# FMC_prototype.net
KiCad netlist of a schematic drawn in EAGLE
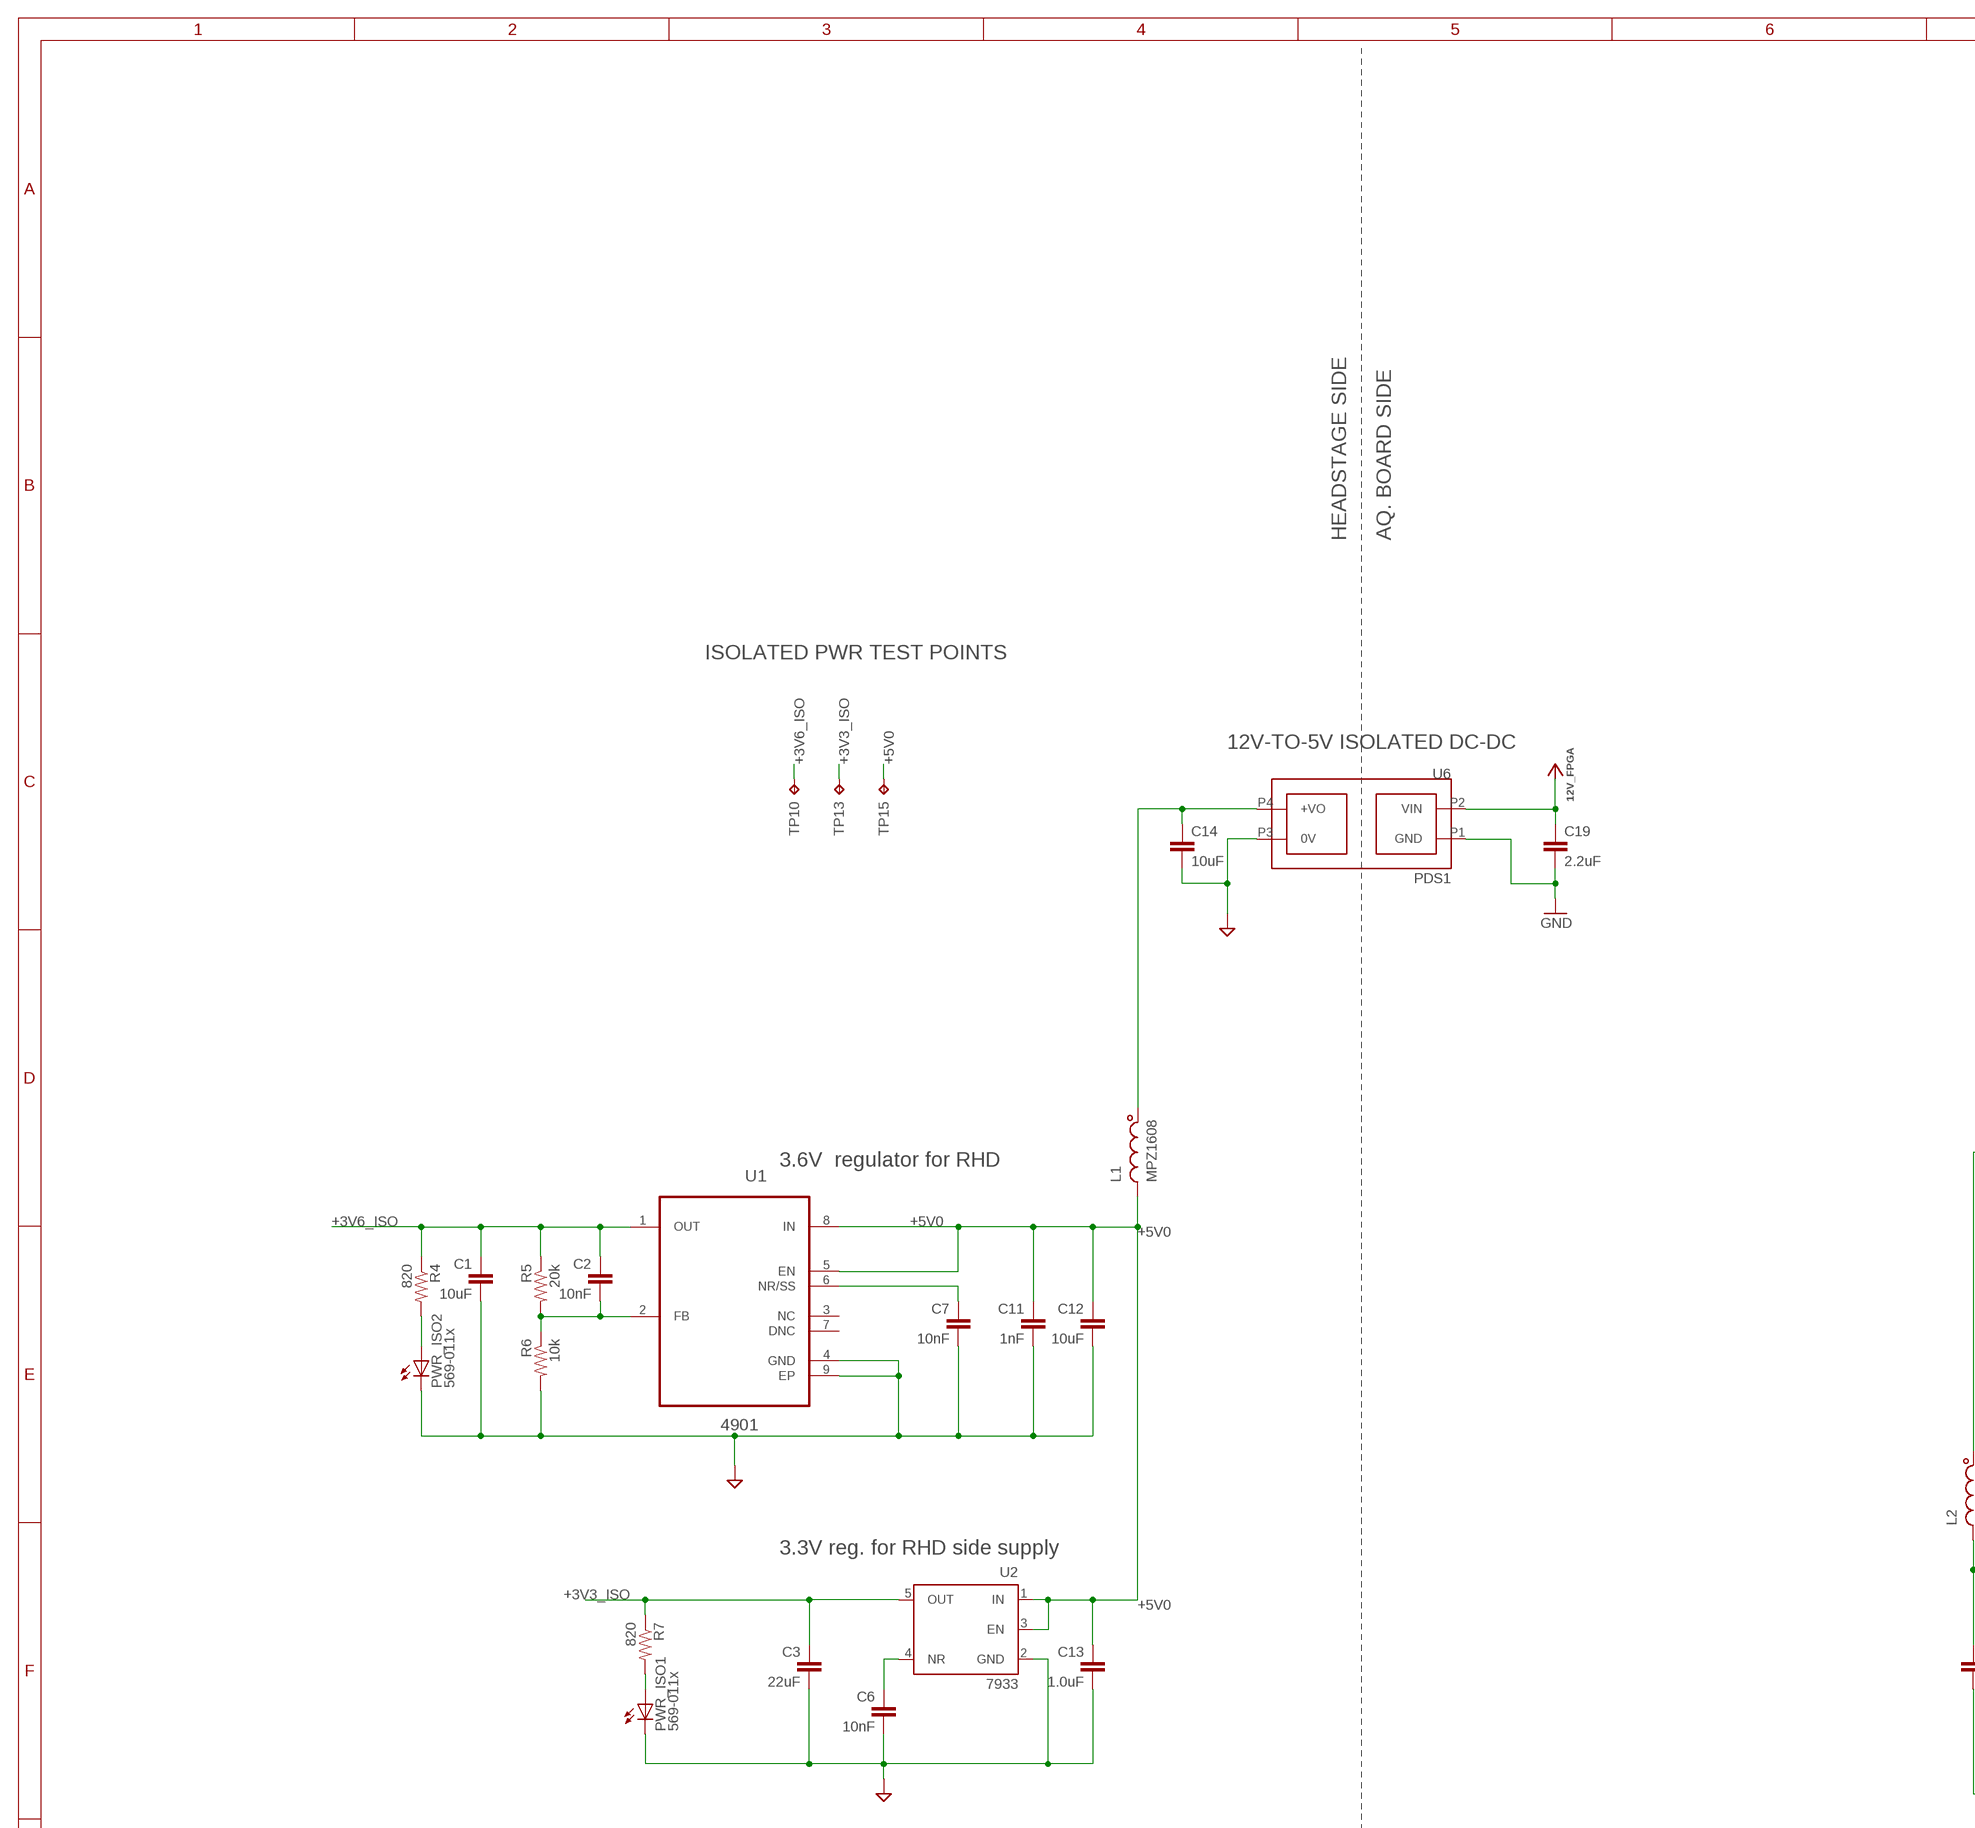
[diagram p0: schematic, sheet 1, part 1 of 3]
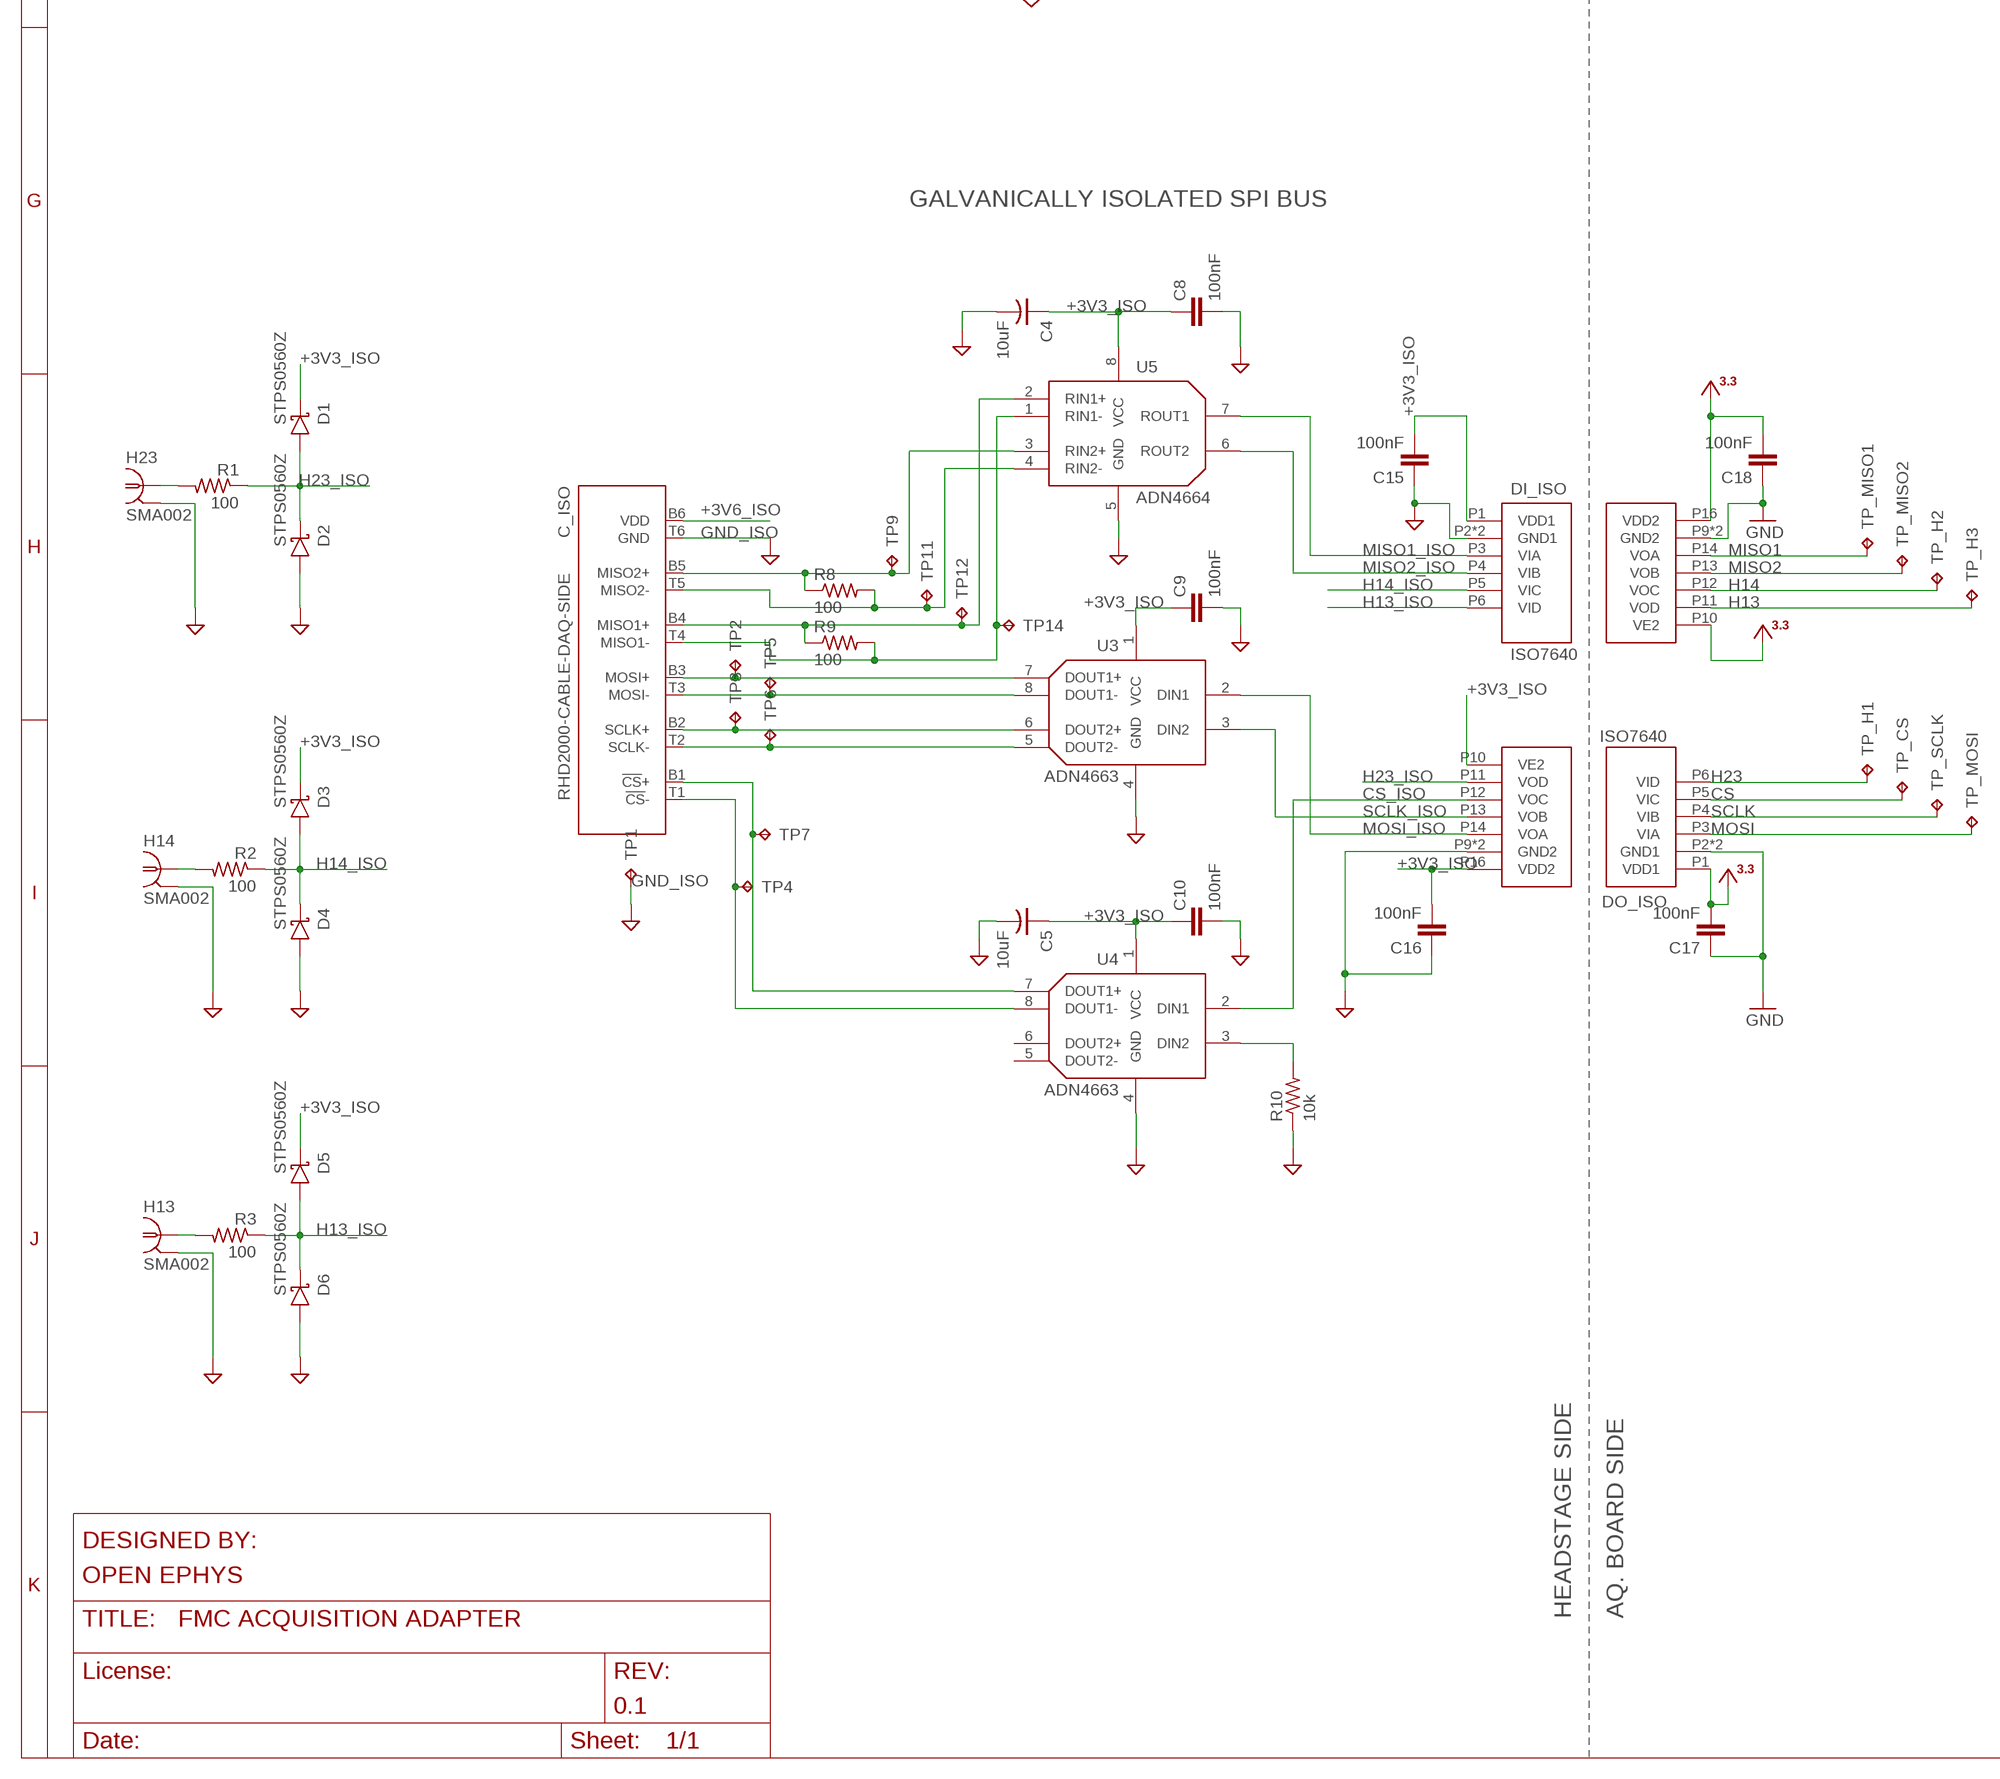
[diagram p1: schematic, sheet 1, part 2 of 3]
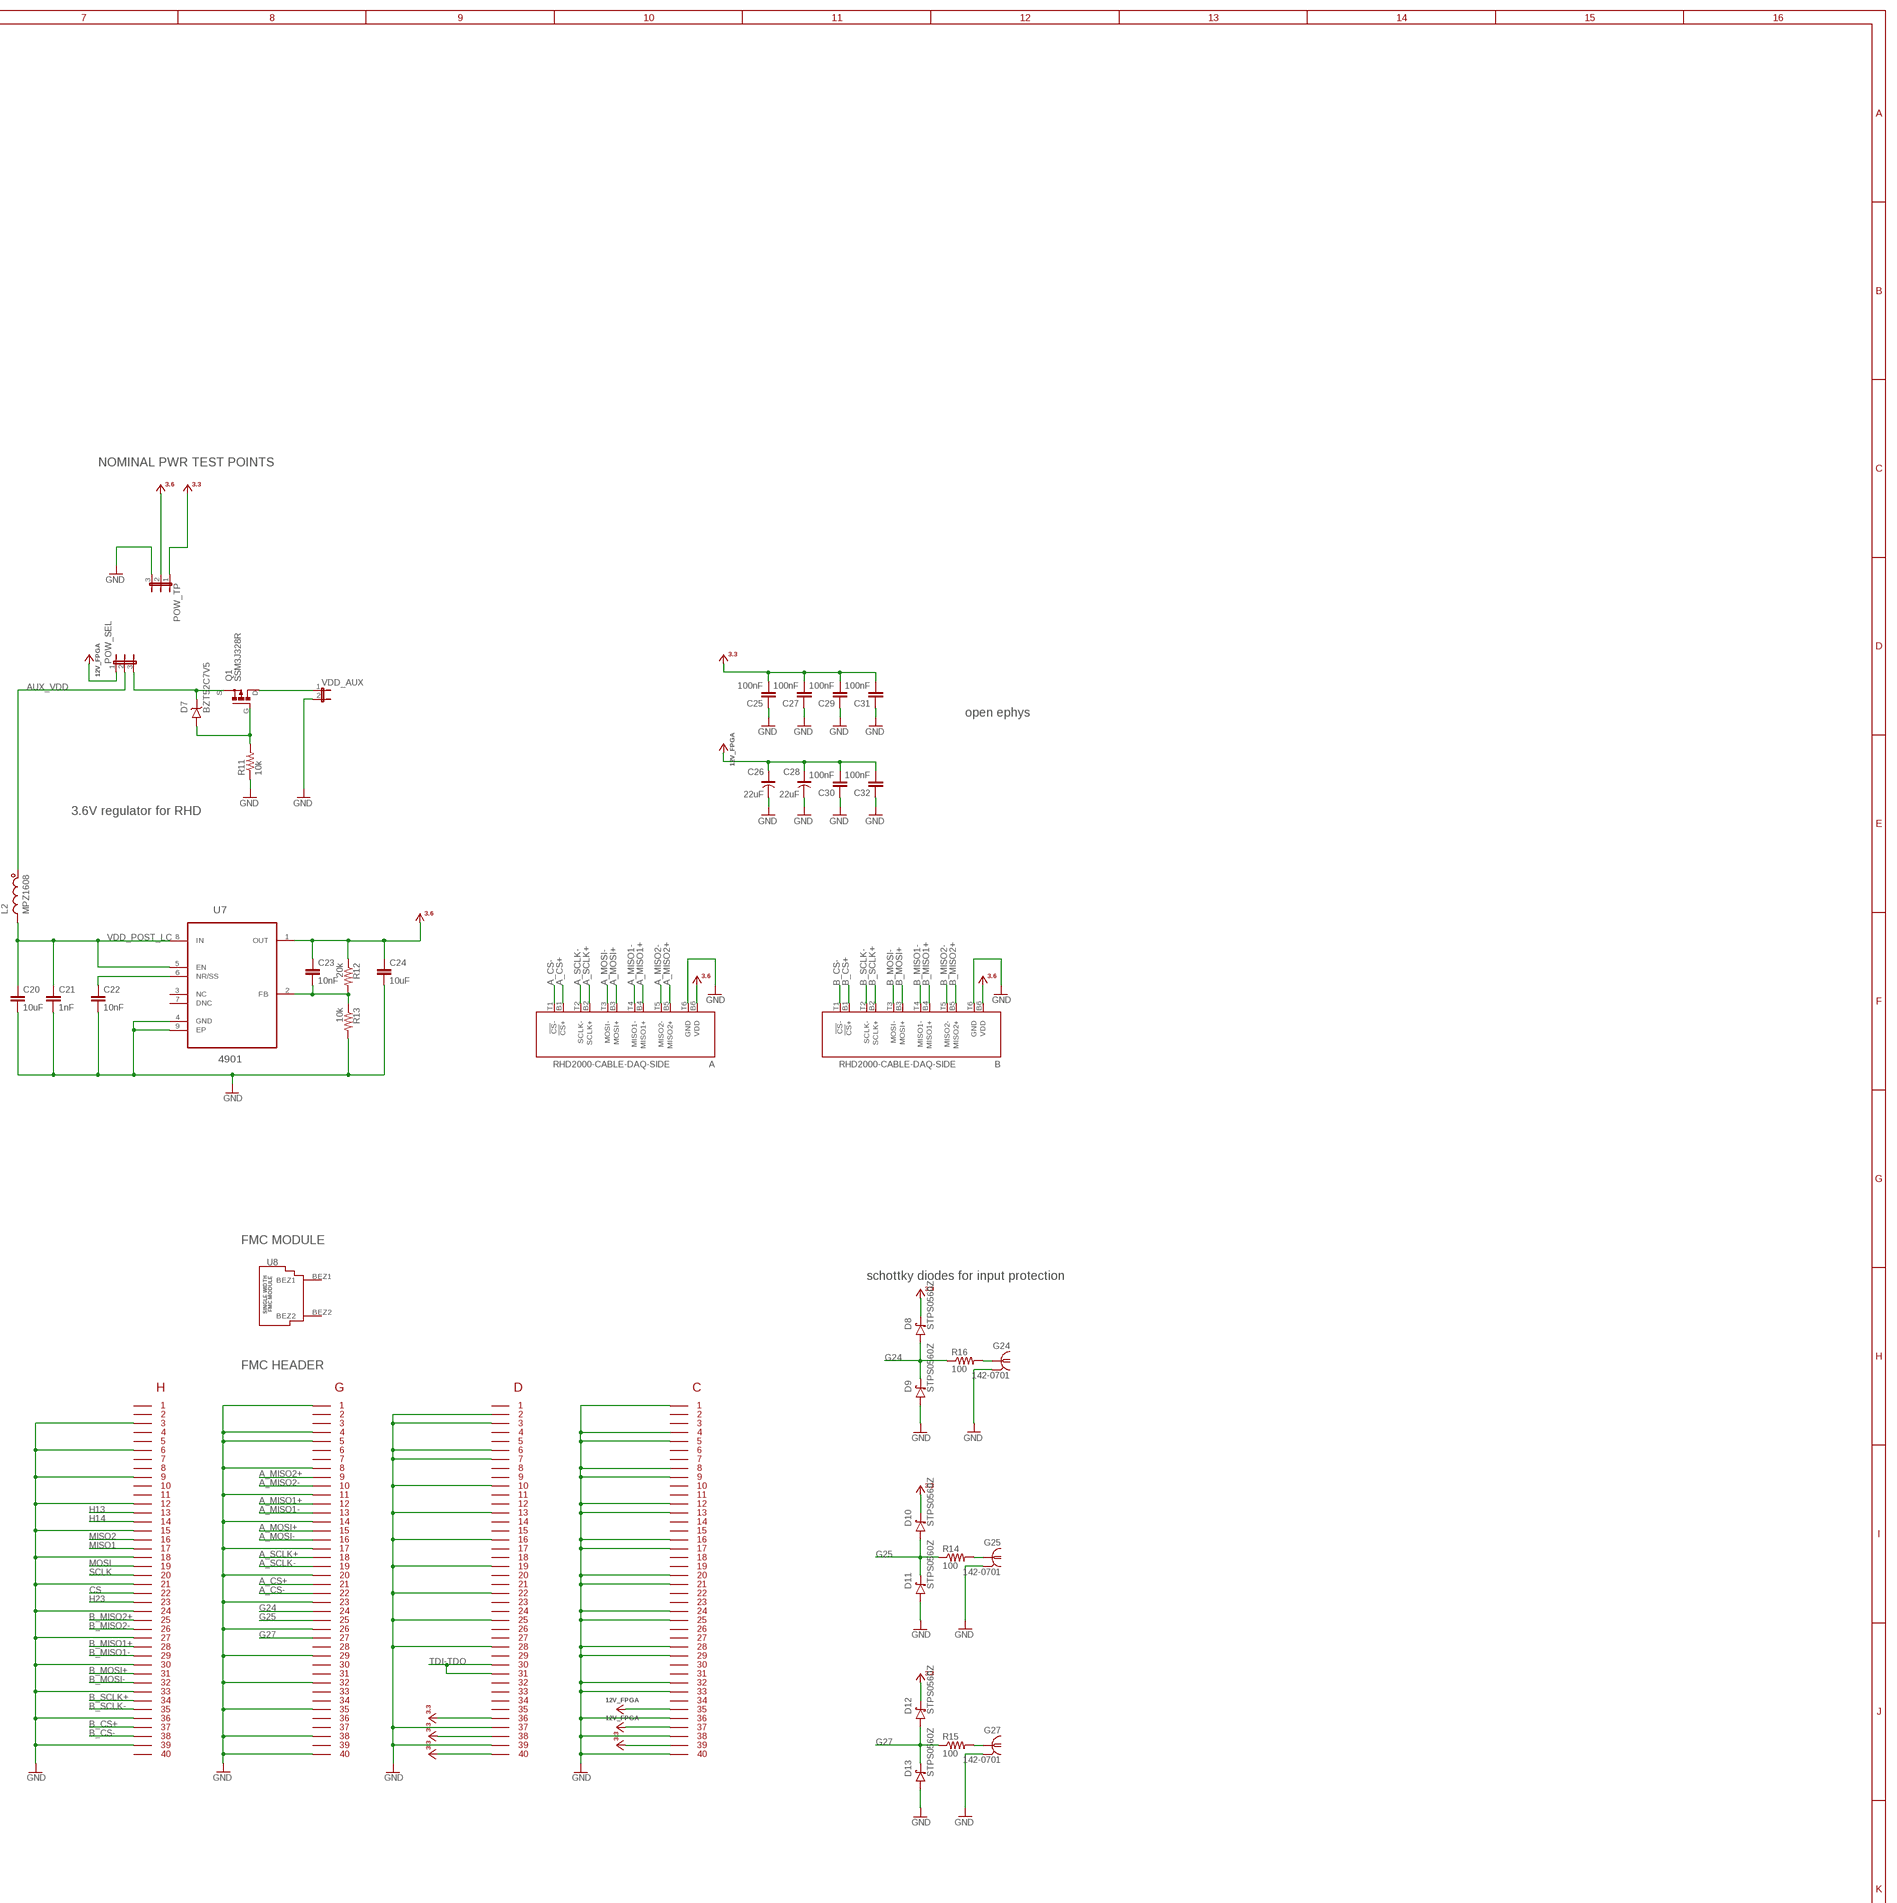
[diagram p2: schematic, sheet 1, part 3 of 3]

(export (version "E")
  (design (tool "Eeschema 10.0.6"))
  (components
    (comp (ref "A")
      (value "RHD2000-CABLE-DAQ-SIDE")
      (footprint "eagle-import:OMNETICS_PZN-12-AA")
      (libsource (lib "eagle-import") (part "RHD2000-CABLE-DAQ-SIDE"))
    )
    (comp (ref "B")
      (value "RHD2000-CABLE-DAQ-SIDE")
      (footprint "eagle-import:OMNETICS_PZN-12-AA")
      (libsource (lib "eagle-import") (part "RHD2000-CABLE-DAQ-SIDE"))
    )
    (comp (ref "C1")
      (value "10uF")
      (footprint "eagle-import:1206")
      (libsource (lib "eagle-import") (part "puggleboard_C_1206"))
    )
    (comp (ref "C2")
      (value "10nF")
      (footprint "eagle-import:0603")
      (libsource (lib "eagle-import") (part "jonnew_C_0603"))
    )
    (comp (ref "C3")
      (value "22uF")
      (footprint "eagle-import:1206")
      (libsource (lib "eagle-import") (part "C_1206"))
    )
    (comp (ref "C4")
      (value "10uF")
      (footprint "eagle-import:1206-POL")
      (libsource (lib "eagle-import") (part "C-POL_1206"))
    )
    (comp (ref "C5")
      (value "10uF")
      (footprint "eagle-import:1206-POL")
      (libsource (lib "eagle-import") (part "C-POL_1206"))
    )
    (comp (ref "C6")
      (value "10nF")
      (footprint "eagle-import:0603")
      (libsource (lib "eagle-import") (part "C_0603"))
    )
    (comp (ref "C7")
      (value "10nF")
      (footprint "eagle-import:0603")
      (libsource (lib "eagle-import") (part "jonnew_C_0603"))
    )
    (comp (ref "C8")
      (value "100nF")
      (footprint "eagle-import:0603")
      (libsource (lib "eagle-import") (part "C_0603"))
    )
    (comp (ref "C9")
      (value "100nF")
      (footprint "eagle-import:0603")
      (libsource (lib "eagle-import") (part "C_0603"))
    )
    (comp (ref "C10")
      (value "100nF")
      (footprint "eagle-import:0603")
      (libsource (lib "eagle-import") (part "C_0603"))
    )
    (comp (ref "C11")
      (value "1nF")
      (footprint "eagle-import:0603")
      (libsource (lib "eagle-import") (part "jonnew_C_0603"))
    )
    (comp (ref "C12")
      (value "10uF")
      (footprint "eagle-import:1206")
      (libsource (lib "eagle-import") (part "puggleboard_C_1206"))
    )
    (comp (ref "C13")
      (value "1.0uF")
      (footprint "eagle-import:0805")
      (libsource (lib "eagle-import") (part "C_0805"))
    )
    (comp (ref "C14")
      (value "10uF")
      (footprint "eagle-import:1206")
      (libsource (lib "eagle-import") (part "jonnew_C_1206"))
    )
    (comp (ref "C15")
      (value "100nF")
      (footprint "eagle-import:0603")
      (libsource (lib "eagle-import") (part "C_0603"))
    )
    (comp (ref "C16")
      (value "100nF")
      (footprint "eagle-import:0603")
      (libsource (lib "eagle-import") (part "C_0603"))
    )
    (comp (ref "C17")
      (value "100nF")
      (footprint "eagle-import:0603")
      (libsource (lib "eagle-import") (part "C_0603"))
    )
    (comp (ref "C18")
      (value "100nF")
      (footprint "eagle-import:0603")
      (libsource (lib "eagle-import") (part "C_0603"))
    )
    (comp (ref "C19")
      (value "2.2uF")
      (footprint "eagle-import:1206")
      (libsource (lib "eagle-import") (part "jonnew_C_1206"))
    )
    (comp (ref "C20")
      (value "10uF")
      (footprint "eagle-import:1206")
      (libsource (lib "eagle-import") (part "puggleboard_C_1206"))
    )
    (comp (ref "C21")
      (value "1nF")
      (footprint "eagle-import:0603")
      (libsource (lib "eagle-import") (part "jonnew_C_0603"))
    )
    (comp (ref "C22")
      (value "10nF")
      (footprint "eagle-import:0603")
      (libsource (lib "eagle-import") (part "jonnew_C_0603"))
    )
    (comp (ref "C23")
      (value "10nF")
      (footprint "eagle-import:0603")
      (libsource (lib "eagle-import") (part "jonnew_C_0603"))
    )
    (comp (ref "C24")
      (value "10uF")
      (footprint "eagle-import:1206")
      (libsource (lib "eagle-import") (part "puggleboard_C_1206"))
    )
    (comp (ref "C25")
      (value "100nF")
      (footprint "eagle-import:0603")
      (libsource (lib "eagle-import") (part "C_0603"))
    )
    (comp (ref "C26")
      (value "22uF")
      (footprint "eagle-import:1210-POL")
      (libsource (lib "eagle-import") (part "C-POL_1210"))
    )
    (comp (ref "C27")
      (value "100nF")
      (footprint "eagle-import:0603")
      (libsource (lib "eagle-import") (part "C_0603"))
    )
    (comp (ref "C28")
      (value "22uF")
      (footprint "eagle-import:1210-POL")
      (libsource (lib "eagle-import") (part "C-POL_1210"))
    )
    (comp (ref "C29")
      (value "100nF")
      (footprint "eagle-import:0603")
      (libsource (lib "eagle-import") (part "C_0603"))
    )
    (comp (ref "C30")
      (value "100nF")
      (footprint "eagle-import:0603")
      (libsource (lib "eagle-import") (part "C_0603"))
    )
    (comp (ref "C31")
      (value "100nF")
      (footprint "eagle-import:0603")
      (libsource (lib "eagle-import") (part "C_0603"))
    )
    (comp (ref "C32")
      (value "100nF")
      (footprint "eagle-import:0603")
      (libsource (lib "eagle-import") (part "C_0603"))
    )
    (comp (ref "C_ISO")
      (value "RHD2000-CABLE-DAQ-SIDE")
      (footprint "eagle-import:OMNETICS_PZN-12-AA")
      (libsource (lib "eagle-import") (part "RHD2000-CABLE-DAQ-SIDE"))
    )
    (comp (ref "D1")
      (value "STPS0560Z")
      (footprint "eagle-import:SOD123")
      (libsource (lib "eagle-import") (part "S-DIODESOD-123"))
    )
    (comp (ref "D2")
      (value "STPS0560Z")
      (footprint "eagle-import:SOD123")
      (libsource (lib "eagle-import") (part "S-DIODESOD-123"))
    )
    (comp (ref "D3")
      (value "STPS0560Z")
      (footprint "eagle-import:SOD123")
      (libsource (lib "eagle-import") (part "S-DIODESOD-123"))
    )
    (comp (ref "D4")
      (value "STPS0560Z")
      (footprint "eagle-import:SOD123")
      (libsource (lib "eagle-import") (part "S-DIODESOD-123"))
    )
    (comp (ref "D5")
      (value "STPS0560Z")
      (footprint "eagle-import:SOD123")
      (libsource (lib "eagle-import") (part "S-DIODESOD-123"))
    )
    (comp (ref "D6")
      (value "STPS0560Z")
      (footprint "eagle-import:SOD123")
      (libsource (lib "eagle-import") (part "S-DIODESOD-123"))
    )
    (comp (ref "D7")
      (value "BZT52C7V5")
      (footprint "eagle-import:SOD123")
      (libsource (lib "eagle-import") (part "Z-DIODE_SOD123"))
    )
    (comp (ref "D8")
      (value "STPS0560Z")
      (footprint "eagle-import:SOD123")
      (libsource (lib "eagle-import") (part "S-DIODESOD-123"))
    )
    (comp (ref "D9")
      (value "STPS0560Z")
      (footprint "eagle-import:SOD123")
      (libsource (lib "eagle-import") (part "S-DIODESOD-123"))
    )
    (comp (ref "D10")
      (value "STPS0560Z")
      (footprint "eagle-import:SOD123")
      (libsource (lib "eagle-import") (part "S-DIODESOD-123"))
    )
    (comp (ref "D11")
      (value "STPS0560Z")
      (footprint "eagle-import:SOD123")
      (libsource (lib "eagle-import") (part "S-DIODESOD-123"))
    )
    (comp (ref "D12")
      (value "STPS0560Z")
      (footprint "eagle-import:SOD123")
      (libsource (lib "eagle-import") (part "S-DIODESOD-123"))
    )
    (comp (ref "D13")
      (value "STPS0560Z")
      (footprint "eagle-import:SOD123")
      (libsource (lib "eagle-import") (part "S-DIODESOD-123"))
    )
    (comp (ref "DI_ISO")
      (value "ISO7640")
      (footprint "eagle-import:SOIC_WIDE_16")
      (libsource (lib "eagle-import") (part "ADUM3440"))
    )
    (comp (ref "DO_ISO")
      (value "ISO7640")
      (footprint "eagle-import:SOIC_WIDE_16")
      (libsource (lib "eagle-import") (part "ADUM3440"))
    )
    (comp (ref "FMC")
      (value "FMC_LPC_160_PIN")
      (footprint "eagle-import:FMC_LPC_MALE_WITH_SP601_BSILK")
      (libsource (lib "eagle-import") (part "FMC_LPC_160_PIN"))
    )
    (comp (ref "G24")
      (value "142-0701")
      (footprint "eagle-import:SMA_JACK_142-0701-201")
      (libsource (lib "eagle-import") (part "COAX_SMA-VERT"))
    )
    (comp (ref "G25")
      (value "142-0701")
      (footprint "eagle-import:SMA_JACK_142-0701-201")
      (libsource (lib "eagle-import") (part "COAX_SMA-VERT"))
    )
    (comp (ref "G27")
      (value "142-0701")
      (footprint "eagle-import:SMA_JACK_142-0701-201")
      (libsource (lib "eagle-import") (part "COAX_SMA-VERT"))
    )
    (comp (ref "H13")
      (value "SMA002")
      (footprint "eagle-import:SMA_JACK_CONREVSMA002-G")
      (libsource (lib "eagle-import") (part "COAX_CONREVSMA002-G"))
    )
    (comp (ref "H14")
      (value "SMA002")
      (footprint "eagle-import:SMA_JACK_CONREVSMA002-G")
      (libsource (lib "eagle-import") (part "COAX_CONREVSMA002-G"))
    )
    (comp (ref "H23")
      (value "SMA002")
      (footprint "eagle-import:SMA_JACK_CONREVSMA002-G")
      (libsource (lib "eagle-import") (part "COAX_CONREVSMA002-G"))
    )
    (comp (ref "L1")
      (value "MPZ1608")
      (footprint "eagle-import:0603")
      (libsource (lib "eagle-import") (part "L_0603"))
    )
    (comp (ref "L2")
      (value "MPZ1608")
      (footprint "eagle-import:0603")
      (libsource (lib "eagle-import") (part "L_0603"))
    )
    (comp (ref "POW_SEL")
      (value "JP3E")
      (footprint "eagle-import:JP3")
      (libsource (lib "eagle-import") (part "JP3E"))
    )
    (comp (ref "POW_TP")
      (value "JP3E")
      (footprint "eagle-import:JP3")
      (libsource (lib "eagle-import") (part "JP3E"))
    )
    (comp (ref "PWR_ISO")
      (value "569-011x")
      (footprint "eagle-import:569-011X-X00_LED_ARRAY")
      (libsource (lib "eagle-import") (part "LED_2X_VERTICAL"))
    )
    (comp (ref "Q1")
      (value "SSM3J328R")
      (footprint "eagle-import:SOT23-GSD")
      (libsource (lib "eagle-import") (part "P-MOSFET_SOT23-GSD"))
    )
    (comp (ref "R1")
      (value "100")
      (footprint "eagle-import:0603")
      (fields (field (name "MPN") "ERJ-3EKFxxxxV"))
      (libsource (lib "eagle-import") (part "jonnew_R_0603"))
    )
    (comp (ref "R2")
      (value "100")
      (footprint "eagle-import:0603")
      (fields (field (name "MPN") "ERJ-3EKFxxxxV"))
      (libsource (lib "eagle-import") (part "jonnew_R_0603"))
    )
    (comp (ref "R3")
      (value "100")
      (footprint "eagle-import:0603")
      (fields (field (name "MPN") "ERJ-3EKFxxxxV"))
      (libsource (lib "eagle-import") (part "jonnew_R_0603"))
    )
    (comp (ref "R4")
      (value "820")
      (footprint "eagle-import:0603")
      (libsource (lib "eagle-import") (part "R_0603"))
    )
    (comp (ref "R5")
      (value "20k")
      (footprint "eagle-import:0603")
      (fields (field (name "MPN") "ERJ-3EKFxxxxV"))
      (libsource (lib "eagle-import") (part "jonnew_R_0603"))
    )
    (comp (ref "R6")
      (value "10k")
      (footprint "eagle-import:0603")
      (fields (field (name "MPN") "ERJ-3EKFxxxxV"))
      (libsource (lib "eagle-import") (part "jonnew_R_0603"))
    )
    (comp (ref "R7")
      (value "820")
      (footprint "eagle-import:0603")
      (libsource (lib "eagle-import") (part "R_0603"))
    )
    (comp (ref "R8")
      (value "100")
      (footprint "eagle-import:0603")
      (libsource (lib "eagle-import") (part "R_0603"))
    )
    (comp (ref "R9")
      (value "100")
      (footprint "eagle-import:0603")
      (libsource (lib "eagle-import") (part "R_0603"))
    )
    (comp (ref "R10")
      (value "10k")
      (footprint "eagle-import:0603")
      (fields (field (name "MPN") "ERJ-3EKFxxxxV"))
      (libsource (lib "eagle-import") (part "jonnew_R_0603"))
    )
    (comp (ref "R11")
      (value "10k")
      (footprint "eagle-import:0603")
      (fields (field (name "MPN") "ERJ-3EKFxxxxV"))
      (libsource (lib "eagle-import") (part "jonnew_R_0603"))
    )
    (comp (ref "R12")
      (value "20k")
      (footprint "eagle-import:0603")
      (fields (field (name "MPN") "ERJ-3EKFxxxxV"))
      (libsource (lib "eagle-import") (part "jonnew_R_0603"))
    )
    (comp (ref "R13")
      (value "10k")
      (footprint "eagle-import:0603")
      (fields (field (name "MPN") "ERJ-3EKFxxxxV"))
      (libsource (lib "eagle-import") (part "jonnew_R_0603"))
    )
    (comp (ref "R14")
      (value "100")
      (footprint "eagle-import:0603")
      (fields (field (name "MPN") "ERJ-3EKFxxxxV"))
      (libsource (lib "eagle-import") (part "jonnew_R_0603"))
    )
    (comp (ref "R15")
      (value "100")
      (footprint "eagle-import:0603")
      (fields (field (name "MPN") "ERJ-3EKFxxxxV"))
      (libsource (lib "eagle-import") (part "jonnew_R_0603"))
    )
    (comp (ref "R16")
      (value "100")
      (footprint "eagle-import:0603")
      (fields (field (name "MPN") "ERJ-3EKFxxxxV"))
      (libsource (lib "eagle-import") (part "jonnew_R_0603"))
    )
    (comp (ref "TP1")
      (value "GND-ISO")
      (footprint "eagle-import:P1-13")
      (libsource (lib "eagle-import") (part "TPPAD1-13"))
    )
    (comp (ref "TP2")
      (value "MOSI+")
      (footprint "eagle-import:TP06R")
      (libsource (lib "eagle-import") (part "TPTP06R"))
    )
    (comp (ref "TP3")
      (value "SCLK+")
      (footprint "eagle-import:TP06R")
      (libsource (lib "eagle-import") (part "TPTP06R"))
    )
    (comp (ref "TP4")
      (value "CS-")
      (footprint "eagle-import:TP06R")
      (libsource (lib "eagle-import") (part "TPTP06R"))
    )
    (comp (ref "TP5")
      (value "MOSI-")
      (footprint "eagle-import:TP06R")
      (libsource (lib "eagle-import") (part "TPTP06R"))
    )
    (comp (ref "TP6")
      (value "SCLK-")
      (footprint "eagle-import:TP06R")
      (libsource (lib "eagle-import") (part "TPTP06R"))
    )
    (comp (ref "TP7")
      (value "CS+")
      (footprint "eagle-import:TP06R")
      (libsource (lib "eagle-import") (part "TPTP06R"))
    )
    (comp (ref "TP9")
      (value "MISO2+")
      (footprint "eagle-import:TP06R")
      (libsource (lib "eagle-import") (part "TPTP06R"))
    )
    (comp (ref "TP10")
      (value "+3V6")
      (footprint "eagle-import:TP06R")
      (libsource (lib "eagle-import") (part "TPTP06R"))
    )
    (comp (ref "TP11")
      (value "MISO2-")
      (footprint "eagle-import:TP06R")
      (libsource (lib "eagle-import") (part "TPTP06R"))
    )
    (comp (ref "TP12")
      (value "MISO1+")
      (footprint "eagle-import:TP06R")
      (libsource (lib "eagle-import") (part "TPTP06R"))
    )
    (comp (ref "TP13")
      (value "+3V3")
      (footprint "eagle-import:TP06R")
      (libsource (lib "eagle-import") (part "TPTP06R"))
    )
    (comp (ref "TP14")
      (value "MISO1-")
      (footprint "eagle-import:TP06R")
      (libsource (lib "eagle-import") (part "TPTP06R"))
    )
    (comp (ref "TP15")
      (value "+5V0")
      (footprint "eagle-import:TP06R")
      (libsource (lib "eagle-import") (part "TPTP06R"))
    )
    (comp (ref "TP_CS")
      (value "CS")
      (footprint "eagle-import:TP06R")
      (libsource (lib "eagle-import") (part "TPTP06R"))
    )
    (comp (ref "TP_H1")
      (value "H23")
      (footprint "eagle-import:TP06R")
      (libsource (lib "eagle-import") (part "TPTP06R"))
    )
    (comp (ref "TP_H2")
      (value "H14")
      (footprint "eagle-import:TP06R")
      (libsource (lib "eagle-import") (part "TPTP06R"))
    )
    (comp (ref "TP_H3")
      (value "H13")
      (footprint "eagle-import:TP06R")
      (libsource (lib "eagle-import") (part "TPTP06R"))
    )
    (comp (ref "TP_MISO1")
      (value "MISO1")
      (footprint "eagle-import:TP06R")
      (libsource (lib "eagle-import") (part "TPTP06R"))
    )
    (comp (ref "TP_MISO2")
      (value "MISO2")
      (footprint "eagle-import:TP06R")
      (libsource (lib "eagle-import") (part "TPTP06R"))
    )
    (comp (ref "TP_MOSI")
      (value "MOSI")
      (footprint "eagle-import:TP06R")
      (libsource (lib "eagle-import") (part "TPTP06R"))
    )
    (comp (ref "TP_SCLK")
      (value "SCLK")
      (footprint "eagle-import:TP06R")
      (libsource (lib "eagle-import") (part "TPTP06R"))
    )
    (comp (ref "U$1")
      (value "OPEN_EPHYS_LOGO")
      (footprint "eagle-import:OPEN_EPHYS_LOGO")
      (libsource (lib "eagle-import") (part "OPEN_EPHYS_LOGO"))
    )
    (comp (ref "U1")
      (value "4901")
      (footprint "eagle-import:SOP65P490X110-9N")
      (fields (field (name "MPN") "TPS7A4901DGNR"))
      (libsource (lib "eagle-import") (part "TPS7A4901DGNR"))
    )
    (comp (ref "U2")
      (value "7933")
      (footprint "eagle-import:SOT-23-5")
      (libsource (lib "eagle-import") (part "TPS79333"))
    )
    (comp (ref "U3")
      (value "ADN4663")
      (footprint "eagle-import:SOIC127P500X400-8N")
      (libsource (lib "eagle-import") (part "ADN4663_SOIC"))
    )
    (comp (ref "U4")
      (value "ADN4663")
      (footprint "eagle-import:SOIC127P500X400-8N")
      (libsource (lib "eagle-import") (part "ADN4663_SOIC"))
    )
    (comp (ref "U5")
      (value "ADN4664")
      (footprint "eagle-import:SOIC127P500X400-8N")
      (libsource (lib "eagle-import") (part "ADN4664_SOIC"))
    )
    (comp (ref "U6")
      (value "PDS1")
      (footprint "eagle-import:PDS1")
      (libsource (lib "eagle-import") (part "PDS1"))
    )
    (comp (ref "U7")
      (value "4901")
      (footprint "eagle-import:SOP65P490X110-9N")
      (fields (field (name "MPN") "TPS7A4901DGNR"))
      (libsource (lib "eagle-import") (part "TPS7A4901DGNR"))
    )
    (comp (ref "U8")
      (value "FMC_SINGLE_WIDTH_MODULE")
      (footprint "eagle-import:FMC_SINGLE_WIDTH_MODULE")
      (libsource (lib "eagle-import") (part "FMC_SINGLE_WIDTH_MODULE"))
    )
    (comp (ref "VDD_AUX")
      (value "JP2E_THRU-HOLE")
      (footprint "eagle-import:JP2")
      (libsource (lib "eagle-import") (part "JP2E_THRU-HOLE"))
    )
  )
  (nets
    (net (code "1") (name "+3V3") (class "Default")
      (node (ref "C17") (pin "2") (pinfunction "2_2") (pintype "passive"))
      (node (ref "C18") (pin "2") (pinfunction "2_2") (pintype "passive"))
      (node (ref "C25") (pin "2") (pinfunction "2_2") (pintype "passive"))
      (node (ref "C27") (pin "2") (pinfunction "2_2") (pintype "passive"))
      (node (ref "C29") (pin "2") (pinfunction "2_2") (pintype "passive"))
      (node (ref "C31") (pin "2") (pinfunction "2_2") (pintype "passive"))
      (node (ref "D10") (pin "C") (pinfunction "C_C") (pintype "passive"))
      (node (ref "D12") (pin "C") (pinfunction "C_C") (pintype "passive"))
      (node (ref "D8") (pin "C") (pinfunction "C_C") (pintype "passive"))
      (node (ref "DI_ISO") (pin "P10") (pinfunction "VE2_P10") (pintype "bidirectional"))
      (node (ref "DI_ISO") (pin "P16") (pinfunction "VDD2_P16") (pintype "bidirectional"))
      (node (ref "DO_ISO") (pin "P1") (pinfunction "VDD1_P1") (pintype "bidirectional"))
      (node (ref "FMC") (pin "P$116") (pinfunction "P$116_P$116") (pintype "bidirectional"))
      (node (ref "FMC") (pin "P$118") (pinfunction "P$118_P$118") (pintype "bidirectional"))
      (node (ref "FMC") (pin "P$120") (pinfunction "P$120_P$120") (pintype "bidirectional"))
      (node (ref "FMC") (pin "P$159") (pinfunction "P$159_P$159") (pintype "bidirectional"))
      (node (ref "POW_TP") (pin "1") (pinfunction "1_1") (pintype "passive"))
    )
    (net (code "2") (name "+3V6") (class "Default")
      (node (ref "A") (pin "B6") (pinfunction "VDD_B6") (pintype "bidirectional"))
      (node (ref "B") (pin "B6") (pinfunction "VDD_B6") (pintype "bidirectional"))
      (node (ref "C23") (pin "1") (pinfunction "1_1") (pintype "passive"))
      (node (ref "C24") (pin "1") (pinfunction "1_1") (pintype "passive"))
      (node (ref "POW_TP") (pin "2") (pinfunction "2_2") (pintype "passive"))
      (node (ref "R12") (pin "1") (pinfunction "1_1") (pintype "passive"))
      (node (ref "U7") (pin "1") (pinfunction "OUT_1") (pintype "passive"))
    )
    (net (code "3") (name "/+3V3_ISO") (class "Default")
      (node (ref "C10") (pin "1") (pinfunction "1_1") (pintype "passive"))
      (node (ref "C15") (pin "2") (pinfunction "2_2") (pintype "passive"))
      (node (ref "C16") (pin "2") (pinfunction "2_2") (pintype "passive"))
      (node (ref "C3") (pin "1") (pinfunction "1_1") (pintype "passive"))
      (node (ref "C4") (pin "+") (pinfunction "+_+") (pintype "passive"))
      (node (ref "C5") (pin "+") (pinfunction "+_+") (pintype "passive"))
      (node (ref "C8") (pin "1") (pinfunction "1_1") (pintype "passive"))
      (node (ref "C9") (pin "1") (pinfunction "1_1") (pintype "passive"))
      (node (ref "D1") (pin "C") (pinfunction "C_C") (pintype "passive"))
      (node (ref "D3") (pin "C") (pinfunction "C_C") (pintype "passive"))
      (node (ref "D5") (pin "C") (pinfunction "C_C") (pintype "passive"))
      (node (ref "DI_ISO") (pin "P1") (pinfunction "VDD1_P1") (pintype "bidirectional"))
      (node (ref "DO_ISO") (pin "P10") (pinfunction "VE2_P10") (pintype "bidirectional"))
      (node (ref "DO_ISO") (pin "P16") (pinfunction "VDD2_P16") (pintype "bidirectional"))
      (node (ref "R7") (pin "1") (pinfunction "1_1") (pintype "passive"))
      (node (ref "TP13") (pin "TP") (pinfunction "TP_TP") (pintype "input"))
      (node (ref "U2") (pin "5") (pinfunction "OUT_5") (pintype "passive"))
      (node (ref "U3") (pin "1") (pinfunction "VCC_1") (pintype "bidirectional"))
      (node (ref "U4") (pin "1") (pinfunction "VCC_1") (pintype "bidirectional"))
      (node (ref "U5") (pin "8") (pinfunction "VCC_8") (pintype "bidirectional"))
    )
    (net (code "4") (name "/+3V6_ISO") (class "Default")
      (node (ref "C1") (pin "1") (pinfunction "1_1") (pintype "passive"))
      (node (ref "C2") (pin "1") (pinfunction "1_1") (pintype "passive"))
      (node (ref "C_ISO") (pin "B6") (pinfunction "VDD_B6") (pintype "bidirectional"))
      (node (ref "R4") (pin "1") (pinfunction "1_1") (pintype "passive"))
      (node (ref "R5") (pin "1") (pinfunction "1_1") (pintype "passive"))
      (node (ref "TP10") (pin "TP") (pinfunction "TP_TP") (pintype "input"))
      (node (ref "U1") (pin "1") (pinfunction "OUT_1") (pintype "passive"))
    )
    (net (code "5") (name "/+5V0") (class "Default")
      (node (ref "C11") (pin "1") (pinfunction "1_1") (pintype "passive"))
      (node (ref "C12") (pin "1") (pinfunction "1_1") (pintype "passive"))
      (node (ref "C13") (pin "1") (pinfunction "1_1") (pintype "passive"))
      (node (ref "L1") (pin "2") (pinfunction "2_2") (pintype "passive"))
      (node (ref "TP15") (pin "TP") (pinfunction "TP_TP") (pintype "input"))
      (node (ref "U1") (pin "5") (pinfunction "EN_5") (pintype "input"))
      (node (ref "U1") (pin "8") (pinfunction "IN_8") (pintype "passive"))
      (node (ref "U2") (pin "1") (pinfunction "IN_1") (pintype "passive"))
      (node (ref "U2") (pin "3") (pinfunction "EN_3") (pintype "input"))
    )
    (net (code "6") (name "/12V_FPGA") (class "Default")
      (node (ref "C19") (pin "1") (pinfunction "1_1") (pintype "passive"))
      (node (ref "C26") (pin "+") (pinfunction "+_+") (pintype "passive"))
      (node (ref "C28") (pin "+") (pinfunction "+_+") (pintype "passive"))
      (node (ref "C30") (pin "2") (pinfunction "2_2") (pintype "passive"))
      (node (ref "C32") (pin "2") (pinfunction "2_2") (pintype "passive"))
      (node (ref "FMC") (pin "P$155") (pinfunction "P$155_P$155") (pintype "bidirectional"))
      (node (ref "FMC") (pin "P$157") (pinfunction "P$157_P$157") (pintype "bidirectional"))
      (node (ref "POW_SEL") (pin "1") (pinfunction "1_1") (pintype "passive"))
      (node (ref "U6") (pin "P2") (pinfunction "VIN_P2") (pintype "bidirectional"))
    )
    (net (code "7") (name "/AUX_VDD") (class "Default")
      (node (ref "L2") (pin "1") (pinfunction "1_1") (pintype "passive"))
      (node (ref "POW_SEL") (pin "2") (pinfunction "2_2") (pintype "passive"))
    )
    (net (code "8") (name "/A_CS+") (class "Default")
      (node (ref "A") (pin "B1") (pinfunction "~{CS}+_B1") (pintype "bidirectional"))
      (node (ref "FMC") (pin "P$61") (pinfunction "P$61_P$61") (pintype "bidirectional"))
    )
    (net (code "9") (name "/A_CS-") (class "Default")
      (node (ref "A") (pin "T1") (pinfunction "~{CS}-_T1") (pintype "bidirectional"))
      (node (ref "FMC") (pin "P$62") (pinfunction "P$62_P$62") (pintype "bidirectional"))
    )
    (net (code "10") (name "/A_MISO1+") (class "Default")
      (node (ref "A") (pin "B4") (pinfunction "MISO1+_B4") (pintype "bidirectional"))
      (node (ref "FMC") (pin "P$52") (pinfunction "P$52_P$52") (pintype "bidirectional"))
    )
    (net (code "11") (name "/A_MISO1-") (class "Default")
      (node (ref "A") (pin "T4") (pinfunction "MISO1-_T4") (pintype "bidirectional"))
      (node (ref "FMC") (pin "P$53") (pinfunction "P$53_P$53") (pintype "bidirectional"))
    )
    (net (code "12") (name "/A_MISO2+") (class "Default")
      (node (ref "A") (pin "B5") (pinfunction "MISO2+_B5") (pintype "bidirectional"))
      (node (ref "FMC") (pin "P$49") (pinfunction "P$49_P$49") (pintype "bidirectional"))
    )
    (net (code "13") (name "/A_MISO2-") (class "Default")
      (node (ref "A") (pin "T5") (pinfunction "MISO2-_T5") (pintype "bidirectional"))
      (node (ref "FMC") (pin "P$50") (pinfunction "P$50_P$50") (pintype "bidirectional"))
    )
    (net (code "14") (name "/A_MOSI+") (class "Default")
      (node (ref "A") (pin "B3") (pinfunction "MOSI+_B3") (pintype "bidirectional"))
      (node (ref "FMC") (pin "P$55") (pinfunction "P$55_P$55") (pintype "bidirectional"))
    )
    (net (code "15") (name "/A_MOSI-") (class "Default")
      (node (ref "A") (pin "T3") (pinfunction "MOSI-_T3") (pintype "bidirectional"))
      (node (ref "FMC") (pin "P$56") (pinfunction "P$56_P$56") (pintype "bidirectional"))
    )
    (net (code "16") (name "/A_SCLK+") (class "Default")
      (node (ref "A") (pin "B2") (pinfunction "SCLK+_B2") (pintype "bidirectional"))
      (node (ref "FMC") (pin "P$58") (pinfunction "P$58_P$58") (pintype "bidirectional"))
    )
    (net (code "17") (name "/A_SCLK-") (class "Default")
      (node (ref "A") (pin "T2") (pinfunction "SCLK-_T2") (pintype "bidirectional"))
      (node (ref "FMC") (pin "P$59") (pinfunction "P$59_P$59") (pintype "bidirectional"))
    )
    (net (code "18") (name "/B_CS+") (class "Default")
      (node (ref "B") (pin "B1") (pinfunction "~{CS}+_B1") (pintype "bidirectional"))
      (node (ref "FMC") (pin "P$37") (pinfunction "P$37_P$37") (pintype "bidirectional"))
    )
    (net (code "19") (name "/B_CS-") (class "Default")
      (node (ref "B") (pin "T1") (pinfunction "~{CS}-_T1") (pintype "bidirectional"))
      (node (ref "FMC") (pin "P$38") (pinfunction "P$38_P$38") (pintype "bidirectional"))
    )
    (net (code "20") (name "/B_MISO1+") (class "Default")
      (node (ref "B") (pin "B4") (pinfunction "MISO1+_B4") (pintype "bidirectional"))
      (node (ref "FMC") (pin "P$28") (pinfunction "P$28_P$28") (pintype "bidirectional"))
    )
    (net (code "21") (name "/B_MISO1-") (class "Default")
      (node (ref "B") (pin "T4") (pinfunction "MISO1-_T4") (pintype "bidirectional"))
      (node (ref "FMC") (pin "P$29") (pinfunction "P$29_P$29") (pintype "bidirectional"))
    )
    (net (code "22") (name "/B_MISO2+") (class "Default")
      (node (ref "B") (pin "B5") (pinfunction "MISO2+_B5") (pintype "bidirectional"))
      (node (ref "FMC") (pin "P$25") (pinfunction "P$25_P$25") (pintype "bidirectional"))
    )
    (net (code "23") (name "/B_MISO2-") (class "Default")
      (node (ref "B") (pin "T5") (pinfunction "MISO2-_T5") (pintype "bidirectional"))
      (node (ref "FMC") (pin "P$26") (pinfunction "P$26_P$26") (pintype "bidirectional"))
    )
    (net (code "24") (name "/B_MOSI+") (class "Default")
      (node (ref "B") (pin "B3") (pinfunction "MOSI+_B3") (pintype "bidirectional"))
      (node (ref "FMC") (pin "P$31") (pinfunction "P$31_P$31") (pintype "bidirectional"))
    )
    (net (code "25") (name "/B_MOSI-") (class "Default")
      (node (ref "B") (pin "T3") (pinfunction "MOSI-_T3") (pintype "bidirectional"))
      (node (ref "FMC") (pin "P$32") (pinfunction "P$32_P$32") (pintype "bidirectional"))
    )
    (net (code "26") (name "/B_SCLK+") (class "Default")
      (node (ref "B") (pin "B2") (pinfunction "SCLK+_B2") (pintype "bidirectional"))
      (node (ref "FMC") (pin "P$34") (pinfunction "P$34_P$34") (pintype "bidirectional"))
    )
    (net (code "27") (name "/B_SCLK-") (class "Default")
      (node (ref "B") (pin "T2") (pinfunction "SCLK-_T2") (pintype "bidirectional"))
      (node (ref "FMC") (pin "P$35") (pinfunction "P$35_P$35") (pintype "bidirectional"))
    )
    (net (code "28") (name "/CS") (class "Default")
      (node (ref "DO_ISO") (pin "P5") (pinfunction "VIC_P5") (pintype "bidirectional"))
      (node (ref "FMC") (pin "P$22") (pinfunction "P$22_P$22") (pintype "bidirectional"))
      (node (ref "TP_CS") (pin "TP") (pinfunction "TP_TP") (pintype "input"))
    )
    (net (code "29") (name "/CS_ISO") (class "Default")
      (node (ref "DO_ISO") (pin "P12") (pinfunction "VOC_P12") (pintype "bidirectional"))
      (node (ref "U4") (pin "2") (pinfunction "DIN1_2") (pintype "bidirectional"))
    )
    (net (code "30") (name "/G24") (class "Default")
      (node (ref "D8") (pin "A") (pinfunction "A_A") (pintype "passive"))
      (node (ref "D9") (pin "C") (pinfunction "C_C") (pintype "passive"))
      (node (ref "FMC") (pin "P$64") (pinfunction "P$64_P$64") (pintype "bidirectional"))
      (node (ref "R16") (pin "1") (pinfunction "1_1") (pintype "passive"))
    )
    (net (code "31") (name "/G25") (class "Default")
      (node (ref "D10") (pin "A") (pinfunction "A_A") (pintype "passive"))
      (node (ref "D11") (pin "C") (pinfunction "C_C") (pintype "passive"))
      (node (ref "FMC") (pin "P$65") (pinfunction "P$65_P$65") (pintype "bidirectional"))
      (node (ref "R14") (pin "1") (pinfunction "1_1") (pintype "passive"))
    )
    (net (code "32") (name "/G27") (class "Default")
      (node (ref "D12") (pin "A") (pinfunction "A_A") (pintype "passive"))
      (node (ref "D13") (pin "C") (pinfunction "C_C") (pintype "passive"))
      (node (ref "FMC") (pin "P$67") (pinfunction "P$67_P$67") (pintype "bidirectional"))
      (node (ref "R15") (pin "1") (pinfunction "1_1") (pintype "passive"))
    )
    (net (code "33") (name "/H13") (class "Default")
      (node (ref "DI_ISO") (pin "P11") (pinfunction "VOD_P11") (pintype "bidirectional"))
      (node (ref "FMC") (pin "P$13") (pinfunction "P$13_P$13") (pintype "bidirectional"))
      (node (ref "TP_H3") (pin "TP") (pinfunction "TP_TP") (pintype "input"))
    )
    (net (code "34") (name "/H13_ISO") (class "Default")
      (node (ref "D5") (pin "A") (pinfunction "A_A") (pintype "passive"))
      (node (ref "D6") (pin "C") (pinfunction "C_C") (pintype "passive"))
      (node (ref "DI_ISO") (pin "P6") (pinfunction "VID_P6") (pintype "bidirectional"))
      (node (ref "R3") (pin "1") (pinfunction "1_1") (pintype "passive"))
    )
    (net (code "35") (name "/H14") (class "Default")
      (node (ref "DI_ISO") (pin "P12") (pinfunction "VOC_P12") (pintype "bidirectional"))
      (node (ref "FMC") (pin "P$14") (pinfunction "P$14_P$14") (pintype "bidirectional"))
      (node (ref "TP_H2") (pin "TP") (pinfunction "TP_TP") (pintype "input"))
    )
    (net (code "36") (name "/H14_ISO") (class "Default")
      (node (ref "D3") (pin "A") (pinfunction "A_A") (pintype "passive"))
      (node (ref "D4") (pin "C") (pinfunction "C_C") (pintype "passive"))
      (node (ref "DI_ISO") (pin "P5") (pinfunction "VIC_P5") (pintype "bidirectional"))
      (node (ref "R2") (pin "1") (pinfunction "1_1") (pintype "passive"))
    )
    (net (code "37") (name "/H23") (class "Default")
      (node (ref "DO_ISO") (pin "P6") (pinfunction "VID_P6") (pintype "bidirectional"))
      (node (ref "FMC") (pin "P$23") (pinfunction "P$23_P$23") (pintype "bidirectional"))
      (node (ref "TP_H1") (pin "TP") (pinfunction "TP_TP") (pintype "input"))
    )
    (net (code "38") (name "/H23_ISO") (class "Default")
      (node (ref "D1") (pin "A") (pinfunction "A_A") (pintype "passive"))
      (node (ref "D2") (pin "C") (pinfunction "C_C") (pintype "passive"))
      (node (ref "DO_ISO") (pin "P11") (pinfunction "VOD_P11") (pintype "bidirectional"))
      (node (ref "R1") (pin "1") (pinfunction "1_1") (pintype "passive"))
    )
    (net (code "39") (name "/MISO1") (class "Default")
      (node (ref "DI_ISO") (pin "P14") (pinfunction "VOA_P14") (pintype "bidirectional"))
      (node (ref "FMC") (pin "P$17") (pinfunction "P$17_P$17") (pintype "bidirectional"))
      (node (ref "TP_MISO1") (pin "TP") (pinfunction "TP_TP") (pintype "input"))
    )
    (net (code "40") (name "/MISO1_ISO") (class "Default")
      (node (ref "DI_ISO") (pin "P3") (pinfunction "VIA_P3") (pintype "bidirectional"))
      (node (ref "U5") (pin "7") (pinfunction "ROUT1_7") (pintype "bidirectional"))
    )
    (net (code "41") (name "/MISO2") (class "Default")
      (node (ref "DI_ISO") (pin "P13") (pinfunction "VOB_P13") (pintype "bidirectional"))
      (node (ref "FMC") (pin "P$16") (pinfunction "P$16_P$16") (pintype "bidirectional"))
      (node (ref "TP_MISO2") (pin "TP") (pinfunction "TP_TP") (pintype "input"))
    )
    (net (code "42") (name "/MISO2_ISO") (class "Default")
      (node (ref "DI_ISO") (pin "P4") (pinfunction "VIB_P4") (pintype "bidirectional"))
      (node (ref "U5") (pin "6") (pinfunction "ROUT2_6") (pintype "bidirectional"))
    )
    (net (code "43") (name "/MOSI") (class "Default")
      (node (ref "DO_ISO") (pin "P3") (pinfunction "VIA_P3") (pintype "bidirectional"))
      (node (ref "FMC") (pin "P$19") (pinfunction "P$19_P$19") (pintype "bidirectional"))
      (node (ref "TP_MOSI") (pin "TP") (pinfunction "TP_TP") (pintype "input"))
    )
    (net (code "44") (name "/MOSI_ISO") (class "Default")
      (node (ref "DO_ISO") (pin "P14") (pinfunction "VOA_P14") (pintype "bidirectional"))
      (node (ref "U3") (pin "2") (pinfunction "DIN1_2") (pintype "bidirectional"))
    )
    (net (code "45") (name "/SCLK") (class "Default")
      (node (ref "DO_ISO") (pin "P4") (pinfunction "VIB_P4") (pintype "bidirectional"))
      (node (ref "FMC") (pin "P$20") (pinfunction "P$20_P$20") (pintype "bidirectional"))
      (node (ref "TP_SCLK") (pin "TP") (pinfunction "TP_TP") (pintype "input"))
    )
    (net (code "46") (name "/SCLK_ISO") (class "Default")
      (node (ref "DO_ISO") (pin "P13") (pinfunction "VOB_P13") (pintype "bidirectional"))
      (node (ref "U3") (pin "3") (pinfunction "DIN2_3") (pintype "bidirectional"))
    )
    (net (code "47") (name "/TDI-TDO") (class "Default")
      (node (ref "FMC") (pin "P$110") (pinfunction "P$110_P$110") (pintype "bidirectional"))
      (node (ref "FMC") (pin "P$111") (pinfunction "P$111_P$111") (pintype "bidirectional"))
    )
    (net (code "48") (name "/VDD_POST_LC") (class "Default")
      (node (ref "C20") (pin "1") (pinfunction "1_1") (pintype "passive"))
      (node (ref "C21") (pin "1") (pinfunction "1_1") (pintype "passive"))
      (node (ref "L2") (pin "2") (pinfunction "2_2") (pintype "passive"))
      (node (ref "U7") (pin "5") (pinfunction "EN_5") (pintype "input"))
      (node (ref "U7") (pin "8") (pinfunction "IN_8") (pintype "passive"))
    )
    (net (code "49") (name "GND") (class "Default")
      (node (ref "A") (pin "T6") (pinfunction "GND_T6") (pintype "power_in"))
      (node (ref "B") (pin "T6") (pinfunction "GND_T6") (pintype "power_in"))
      (node (ref "C17") (pin "1") (pinfunction "1_1") (pintype "passive"))
      (node (ref "C18") (pin "1") (pinfunction "1_1") (pintype "passive"))
      (node (ref "C19") (pin "2") (pinfunction "2_2") (pintype "passive"))
      (node (ref "C20") (pin "2") (pinfunction "2_2") (pintype "passive"))
      (node (ref "C21") (pin "2") (pinfunction "2_2") (pintype "passive"))
      (node (ref "C22") (pin "2") (pinfunction "2_2") (pintype "passive"))
      (node (ref "C24") (pin "2") (pinfunction "2_2") (pintype "passive"))
      (node (ref "C25") (pin "1") (pinfunction "1_1") (pintype "passive"))
      (node (ref "C26") (pin "-") (pinfunction "-_-") (pintype "passive"))
      (node (ref "C27") (pin "1") (pinfunction "1_1") (pintype "passive"))
      (node (ref "C28") (pin "-") (pinfunction "-_-") (pintype "passive"))
      (node (ref "C29") (pin "1") (pinfunction "1_1") (pintype "passive"))
      (node (ref "C30") (pin "1") (pinfunction "1_1") (pintype "passive"))
      (node (ref "C31") (pin "1") (pinfunction "1_1") (pintype "passive"))
      (node (ref "C32") (pin "1") (pinfunction "1_1") (pintype "passive"))
      (node (ref "D11") (pin "A") (pinfunction "A_A") (pintype "passive"))
      (node (ref "D13") (pin "A") (pinfunction "A_A") (pintype "passive"))
      (node (ref "D9") (pin "A") (pinfunction "A_A") (pintype "passive"))
      (node (ref "DI_ISO") (pin "P15") (pinfunction "GND2_P15") (pintype "bidirectional"))
      (node (ref "DI_ISO") (pin "P9") (pinfunction "GND2_P9") (pintype "bidirectional"))
      (node (ref "DO_ISO") (pin "P2") (pinfunction "GND1_P2") (pintype "bidirectional"))
      (node (ref "DO_ISO") (pin "P8") (pinfunction "GND1_P8") (pintype "bidirectional"))
      (node (ref "FMC") (pin "P$102") (pinfunction "P$102_P$102") (pintype "bidirectional"))
      (node (ref "FMC") (pin "P$105") (pinfunction "P$105_P$105") (pintype "bidirectional"))
      (node (ref "FMC") (pin "P$108") (pinfunction "P$108_P$108") (pintype "bidirectional"))
      (node (ref "FMC") (pin "P$117") (pinfunction "P$117_P$117") (pintype "bidirectional"))
      (node (ref "FMC") (pin "P$119") (pinfunction "P$119_P$119") (pintype "bidirectional"))
      (node (ref "FMC") (pin "P$12") (pinfunction "P$12_P$12") (pintype "bidirectional"))
      (node (ref "FMC") (pin "P$121") (pinfunction "P$121_P$121") (pintype "bidirectional"))
      (node (ref "FMC") (pin "P$124") (pinfunction "P$124_P$124") (pintype "bidirectional"))
      (node (ref "FMC") (pin "P$125") (pinfunction "P$125_P$125") (pintype "bidirectional"))
      (node (ref "FMC") (pin "P$128") (pinfunction "P$128_P$128") (pintype "bidirectional"))
      (node (ref "FMC") (pin "P$129") (pinfunction "P$129_P$129") (pintype "bidirectional"))
      (node (ref "FMC") (pin "P$132") (pinfunction "P$132_P$132") (pintype "bidirectional"))
      (node (ref "FMC") (pin "P$133") (pinfunction "P$133_P$133") (pintype "bidirectional"))
      (node (ref "FMC") (pin "P$136") (pinfunction "P$136_P$136") (pintype "bidirectional"))
      (node (ref "FMC") (pin "P$137") (pinfunction "P$137_P$137") (pintype "bidirectional"))
      (node (ref "FMC") (pin "P$140") (pinfunction "P$140_P$140") (pintype "bidirectional"))
      (node (ref "FMC") (pin "P$141") (pinfunction "P$141_P$141") (pintype "bidirectional"))
      (node (ref "FMC") (pin "P$144") (pinfunction "P$144_P$144") (pintype "bidirectional"))
      (node (ref "FMC") (pin "P$145") (pinfunction "P$145_P$145") (pintype "bidirectional"))
      (node (ref "FMC") (pin "P$148") (pinfunction "P$148_P$148") (pintype "bidirectional"))
      (node (ref "FMC") (pin "P$149") (pinfunction "P$149_P$149") (pintype "bidirectional"))
      (node (ref "FMC") (pin "P$15") (pinfunction "P$15_P$15") (pintype "bidirectional"))
      (node (ref "FMC") (pin "P$152") (pinfunction "P$152_P$152") (pintype "bidirectional"))
      (node (ref "FMC") (pin "P$153") (pinfunction "P$153_P$153") (pintype "bidirectional"))
      (node (ref "FMC") (pin "P$156") (pinfunction "P$156_P$156") (pintype "bidirectional"))
      (node (ref "FMC") (pin "P$158") (pinfunction "P$158_P$158") (pintype "bidirectional"))
      (node (ref "FMC") (pin "P$160") (pinfunction "P$160_P$160") (pintype "bidirectional"))
      (node (ref "FMC") (pin "P$18") (pinfunction "P$18_P$18") (pintype "bidirectional"))
      (node (ref "FMC") (pin "P$21") (pinfunction "P$21_P$21") (pintype "bidirectional"))
      (node (ref "FMC") (pin "P$24") (pinfunction "P$24_P$24") (pintype "bidirectional"))
      (node (ref "FMC") (pin "P$27") (pinfunction "P$27_P$27") (pintype "bidirectional"))
      (node (ref "FMC") (pin "P$3") (pinfunction "P$3_P$3") (pintype "bidirectional"))
      (node (ref "FMC") (pin "P$30") (pinfunction "P$30_P$30") (pintype "bidirectional"))
      (node (ref "FMC") (pin "P$33") (pinfunction "P$33_P$33") (pintype "bidirectional"))
      (node (ref "FMC") (pin "P$36") (pinfunction "P$36_P$36") (pintype "bidirectional"))
      (node (ref "FMC") (pin "P$39") (pinfunction "P$39_P$39") (pintype "bidirectional"))
      (node (ref "FMC") (pin "P$41") (pinfunction "P$41_P$41") (pintype "bidirectional"))
      (node (ref "FMC") (pin "P$44") (pinfunction "P$44_P$44") (pintype "bidirectional"))
      (node (ref "FMC") (pin "P$45") (pinfunction "P$45_P$45") (pintype "bidirectional"))
      (node (ref "FMC") (pin "P$48") (pinfunction "P$48_P$48") (pintype "bidirectional"))
      (node (ref "FMC") (pin "P$51") (pinfunction "P$51_P$51") (pintype "bidirectional"))
      (node (ref "FMC") (pin "P$54") (pinfunction "P$54_P$54") (pintype "bidirectional"))
      (node (ref "FMC") (pin "P$57") (pinfunction "P$57_P$57") (pintype "bidirectional"))
      (node (ref "FMC") (pin "P$6") (pinfunction "P$6_P$6") (pintype "bidirectional"))
      (node (ref "FMC") (pin "P$60") (pinfunction "P$60_P$60") (pintype "bidirectional"))
      (node (ref "FMC") (pin "P$63") (pinfunction "P$63_P$63") (pintype "bidirectional"))
      (node (ref "FMC") (pin "P$66") (pinfunction "P$66_P$66") (pintype "bidirectional"))
      (node (ref "FMC") (pin "P$69") (pinfunction "P$69_P$69") (pintype "bidirectional"))
      (node (ref "FMC") (pin "P$72") (pinfunction "P$72_P$72") (pintype "bidirectional"))
      (node (ref "FMC") (pin "P$75") (pinfunction "P$75_P$75") (pintype "bidirectional"))
      (node (ref "FMC") (pin "P$78") (pinfunction "P$78_P$78") (pintype "bidirectional"))
      (node (ref "FMC") (pin "P$80") (pinfunction "P$80_P$80") (pintype "bidirectional"))
      (node (ref "FMC") (pin "P$82") (pinfunction "P$82_P$82") (pintype "bidirectional"))
      (node (ref "FMC") (pin "P$83") (pinfunction "P$83_P$83") (pintype "bidirectional"))
      (node (ref "FMC") (pin "P$86") (pinfunction "P$86_P$86") (pintype "bidirectional"))
      (node (ref "FMC") (pin "P$87") (pinfunction "P$87_P$87") (pintype "bidirectional"))
      (node (ref "FMC") (pin "P$9") (pinfunction "P$9_P$9") (pintype "bidirectional"))
      (node (ref "FMC") (pin "P$90") (pinfunction "P$90_P$90") (pintype "bidirectional"))
      (node (ref "FMC") (pin "P$93") (pinfunction "P$93_P$93") (pintype "bidirectional"))
      (node (ref "FMC") (pin "P$96") (pinfunction "P$96_P$96") (pintype "bidirectional"))
      (node (ref "FMC") (pin "P$99") (pinfunction "P$99_P$99") (pintype "bidirectional"))
      (node (ref "G24") (pin "GND$1") (pinfunction "2_GND$1") (pintype "passive"))
      (node (ref "G24") (pin "GND$2") (pinfunction "2_GND$2") (pintype "passive"))
      (node (ref "G24") (pin "GND$3") (pinfunction "2_GND$3") (pintype "passive"))
      (node (ref "G24") (pin "GND$4") (pinfunction "2_GND$4") (pintype "passive"))
      (node (ref "G25") (pin "GND$1") (pinfunction "2_GND$1") (pintype "passive"))
      (node (ref "G25") (pin "GND$2") (pinfunction "2_GND$2") (pintype "passive"))
      (node (ref "G25") (pin "GND$3") (pinfunction "2_GND$3") (pintype "passive"))
      (node (ref "G25") (pin "GND$4") (pinfunction "2_GND$4") (pintype "passive"))
      (node (ref "G27") (pin "GND$1") (pinfunction "2_GND$1") (pintype "passive"))
      (node (ref "G27") (pin "GND$2") (pinfunction "2_GND$2") (pintype "passive"))
      (node (ref "G27") (pin "GND$3") (pinfunction "2_GND$3") (pintype "passive"))
      (node (ref "G27") (pin "GND$4") (pinfunction "2_GND$4") (pintype "passive"))
      (node (ref "POW_TP") (pin "3") (pinfunction "3_3") (pintype "passive"))
      (node (ref "R11") (pin "1") (pinfunction "1_1") (pintype "passive"))
      (node (ref "R13") (pin "2") (pinfunction "2_2") (pintype "passive"))
      (node (ref "U6") (pin "P1") (pinfunction "GND_P1") (pintype "bidirectional"))
      (node (ref "U7") (pin "4") (pinfunction "GND_4") (pintype "passive"))
      (node (ref "U7") (pin "9") (pinfunction "EP_9") (pintype "passive"))
      (node (ref "VDD_AUX") (pin "2") (pinfunction "2_2") (pintype "passive"))
    )
    (net (code "50") (name "GND_ISO") (class "Default")
      (node (ref "C1") (pin "2") (pinfunction "2_2") (pintype "passive"))
      (node (ref "C10") (pin "2") (pinfunction "2_2") (pintype "passive"))
      (node (ref "C11") (pin "2") (pinfunction "2_2") (pintype "passive"))
      (node (ref "C12") (pin "2") (pinfunction "2_2") (pintype "passive"))
      (node (ref "C13") (pin "2") (pinfunction "2_2") (pintype "passive"))
      (node (ref "C14") (pin "2") (pinfunction "2_2") (pintype "passive"))
      (node (ref "C15") (pin "1") (pinfunction "1_1") (pintype "passive"))
      (node (ref "C16") (pin "1") (pinfunction "1_1") (pintype "passive"))
      (node (ref "C3") (pin "2") (pinfunction "2_2") (pintype "passive"))
      (node (ref "C4") (pin "-") (pinfunction "-_-") (pintype "passive"))
      (node (ref "C5") (pin "-") (pinfunction "-_-") (pintype "passive"))
      (node (ref "C6") (pin "2") (pinfunction "2_2") (pintype "passive"))
      (node (ref "C7") (pin "2") (pinfunction "2_2") (pintype "passive"))
      (node (ref "C8") (pin "2") (pinfunction "2_2") (pintype "passive"))
      (node (ref "C9") (pin "2") (pinfunction "2_2") (pintype "passive"))
      (node (ref "C_ISO") (pin "T6") (pinfunction "GND_T6") (pintype "power_in"))
      (node (ref "D2") (pin "A") (pinfunction "A_A") (pintype "passive"))
      (node (ref "D4") (pin "A") (pinfunction "A_A") (pintype "passive"))
      (node (ref "D6") (pin "A") (pinfunction "A_A") (pintype "passive"))
      (node (ref "DI_ISO") (pin "P2") (pinfunction "GND1_P2") (pintype "bidirectional"))
      (node (ref "DI_ISO") (pin "P8") (pinfunction "GND1_P8") (pintype "bidirectional"))
      (node (ref "DO_ISO") (pin "P15") (pinfunction "GND2_P15") (pintype "bidirectional"))
      (node (ref "DO_ISO") (pin "P9") (pinfunction "GND2_P9") (pintype "bidirectional"))
      (node (ref "H13") (pin "GND$1") (pinfunction "2_GND$1") (pintype "passive"))
      (node (ref "H13") (pin "GND$2") (pinfunction "2_GND$2") (pintype "passive"))
      (node (ref "H13") (pin "GND$3") (pinfunction "2_GND$3") (pintype "passive"))
      (node (ref "H13") (pin "GND$4") (pinfunction "2_GND$4") (pintype "passive"))
      (node (ref "H14") (pin "GND$1") (pinfunction "2_GND$1") (pintype "passive"))
      (node (ref "H14") (pin "GND$2") (pinfunction "2_GND$2") (pintype "passive"))
      (node (ref "H14") (pin "GND$3") (pinfunction "2_GND$3") (pintype "passive"))
      (node (ref "H14") (pin "GND$4") (pinfunction "2_GND$4") (pintype "passive"))
      (node (ref "H23") (pin "GND$1") (pinfunction "2_GND$1") (pintype "passive"))
      (node (ref "H23") (pin "GND$2") (pinfunction "2_GND$2") (pintype "passive"))
      (node (ref "H23") (pin "GND$3") (pinfunction "2_GND$3") (pintype "passive"))
      (node (ref "H23") (pin "GND$4") (pinfunction "2_GND$4") (pintype "passive"))
      (node (ref "PWR_ISO") (pin "C1") (pinfunction "C_C1") (pintype "passive"))
      (node (ref "PWR_ISO") (pin "C2") (pinfunction "C_C2") (pintype "passive"))
      (node (ref "R10") (pin "1") (pinfunction "1_1") (pintype "passive"))
      (node (ref "R6") (pin "2") (pinfunction "2_2") (pintype "passive"))
      (node (ref "TP1") (pin "TP") (pinfunction "TP_TP") (pintype "input"))
      (node (ref "U1") (pin "4") (pinfunction "GND_4") (pintype "passive"))
      (node (ref "U1") (pin "9") (pinfunction "EP_9") (pintype "passive"))
      (node (ref "U2") (pin "2") (pinfunction "GND_2") (pintype "passive"))
      (node (ref "U3") (pin "4") (pinfunction "GND_4") (pintype "bidirectional"))
      (node (ref "U4") (pin "4") (pinfunction "GND_4") (pintype "bidirectional"))
      (node (ref "U5") (pin "5") (pinfunction "GND_5") (pintype "bidirectional"))
      (node (ref "U6") (pin "P3") (pinfunction "0V_P3") (pintype "bidirectional"))
    )
    (net (code "51") (name "Net-(C_ISO-MISO1+)") (class "Default")
      (node (ref "C_ISO") (pin "B4") (pinfunction "MISO1+_B4") (pintype "bidirectional"))
      (node (ref "R9") (pin "1") (pinfunction "1_1") (pintype "passive"))
      (node (ref "TP12") (pin "TP") (pinfunction "TP_TP") (pintype "input"))
      (node (ref "U5") (pin "2") (pinfunction "RIN1+_2") (pintype "bidirectional"))
    )
    (net (code "52") (name "Net-(C_ISO-MISO1-)") (class "Default")
      (node (ref "C_ISO") (pin "T4") (pinfunction "MISO1-_T4") (pintype "bidirectional"))
      (node (ref "R9") (pin "2") (pinfunction "2_2") (pintype "passive"))
      (node (ref "TP14") (pin "TP") (pinfunction "TP_TP") (pintype "input"))
      (node (ref "U5") (pin "1") (pinfunction "RIN1-_1") (pintype "bidirectional"))
    )
    (net (code "53") (name "Net-(C_ISO-MISO2+)") (class "Default")
      (node (ref "C_ISO") (pin "B5") (pinfunction "MISO2+_B5") (pintype "bidirectional"))
      (node (ref "R8") (pin "1") (pinfunction "1_1") (pintype "passive"))
      (node (ref "TP9") (pin "TP") (pinfunction "TP_TP") (pintype "input"))
      (node (ref "U5") (pin "3") (pinfunction "RIN2+_3") (pintype "bidirectional"))
    )
    (net (code "54") (name "Net-(C_ISO-MISO2-)") (class "Default")
      (node (ref "C_ISO") (pin "T5") (pinfunction "MISO2-_T5") (pintype "bidirectional"))
      (node (ref "R8") (pin "2") (pinfunction "2_2") (pintype "passive"))
      (node (ref "TP11") (pin "TP") (pinfunction "TP_TP") (pintype "input"))
      (node (ref "U5") (pin "4") (pinfunction "RIN2-_4") (pintype "bidirectional"))
    )
    (net (code "55") (name "Net-(C_ISO-MOSI+)") (class "Default")
      (node (ref "C_ISO") (pin "B3") (pinfunction "MOSI+_B3") (pintype "bidirectional"))
      (node (ref "TP2") (pin "TP") (pinfunction "TP_TP") (pintype "input"))
      (node (ref "U3") (pin "7") (pinfunction "DOUT1+_7") (pintype "bidirectional"))
    )
    (net (code "56") (name "Net-(C_ISO-MOSI-)") (class "Default")
      (node (ref "C_ISO") (pin "T3") (pinfunction "MOSI-_T3") (pintype "bidirectional"))
      (node (ref "TP5") (pin "TP") (pinfunction "TP_TP") (pintype "input"))
      (node (ref "U3") (pin "8") (pinfunction "DOUT1-_8") (pintype "bidirectional"))
    )
    (net (code "57") (name "Net-(C_ISO-SCLK+)") (class "Default")
      (node (ref "C_ISO") (pin "B2") (pinfunction "SCLK+_B2") (pintype "bidirectional"))
      (node (ref "TP3") (pin "TP") (pinfunction "TP_TP") (pintype "input"))
      (node (ref "U3") (pin "6") (pinfunction "DOUT2+_6") (pintype "bidirectional"))
    )
    (net (code "58") (name "Net-(C_ISO-SCLK-)") (class "Default")
      (node (ref "C_ISO") (pin "T2") (pinfunction "SCLK-_T2") (pintype "bidirectional"))
      (node (ref "TP6") (pin "TP") (pinfunction "TP_TP") (pintype "input"))
      (node (ref "U3") (pin "5") (pinfunction "DOUT2-_5") (pintype "bidirectional"))
    )
    (net (code "59") (name "Net-(C_ISO-~{CS}+)") (class "Default")
      (node (ref "C_ISO") (pin "B1") (pinfunction "~{CS}+_B1") (pintype "bidirectional"))
      (node (ref "TP7") (pin "TP") (pinfunction "TP_TP") (pintype "input"))
      (node (ref "U4") (pin "7") (pinfunction "DOUT1+_7") (pintype "bidirectional"))
    )
    (net (code "60") (name "Net-(C_ISO-~{CS}-)") (class "Default")
      (node (ref "C_ISO") (pin "T1") (pinfunction "~{CS}-_T1") (pintype "bidirectional"))
      (node (ref "TP4") (pin "TP") (pinfunction "TP_TP") (pintype "input"))
      (node (ref "U4") (pin "8") (pinfunction "DOUT1-_8") (pintype "bidirectional"))
    )
    (net (code "61") (name "Net-(D7-PadA)") (class "Default")
      (node (ref "D7") (pin "A") (pinfunction "A_A") (pintype "passive"))
      (node (ref "Q1") (pin "G") (pinfunction "G_G") (pintype "bidirectional"))
      (node (ref "R11") (pin "2") (pinfunction "2_2") (pintype "passive"))
    )
    (net (code "62") (name "Net-(D7-PadC)") (class "Default")
      (node (ref "D7") (pin "C") (pinfunction "C_C") (pintype "passive"))
      (node (ref "POW_SEL") (pin "3") (pinfunction "3_3") (pintype "passive"))
      (node (ref "Q1") (pin "S") (pinfunction "S_S") (pintype "bidirectional"))
    )
    (net (code "63") (name "Net-(G24-1)") (class "Default")
      (node (ref "G24") (pin "CLK") (pinfunction "1_CLK") (pintype "passive"))
      (node (ref "R16") (pin "2") (pinfunction "2_2") (pintype "passive"))
    )
    (net (code "64") (name "Net-(G25-1)") (class "Default")
      (node (ref "G25") (pin "CLK") (pinfunction "1_CLK") (pintype "passive"))
      (node (ref "R14") (pin "2") (pinfunction "2_2") (pintype "passive"))
    )
    (net (code "65") (name "Net-(G27-1)") (class "Default")
      (node (ref "G27") (pin "CLK") (pinfunction "1_CLK") (pintype "passive"))
      (node (ref "R15") (pin "2") (pinfunction "2_2") (pintype "passive"))
    )
    (net (code "66") (name "Net-(H13-1)") (class "Default")
      (node (ref "H13") (pin "CLK") (pinfunction "1_CLK") (pintype "passive"))
      (node (ref "R3") (pin "2") (pinfunction "2_2") (pintype "passive"))
    )
    (net (code "67") (name "Net-(H14-1)") (class "Default")
      (node (ref "H14") (pin "CLK") (pinfunction "1_CLK") (pintype "passive"))
      (node (ref "R2") (pin "2") (pinfunction "2_2") (pintype "passive"))
    )
    (net (code "68") (name "Net-(H23-1)") (class "Default")
      (node (ref "H23") (pin "CLK") (pinfunction "1_CLK") (pintype "passive"))
      (node (ref "R1") (pin "2") (pinfunction "2_2") (pintype "passive"))
    )
    (net (code "69") (name "Net-(PWR_ISOA-A)") (class "Default")
      (node (ref "PWR_ISO") (pin "A1") (pinfunction "A_A1") (pintype "passive"))
      (node (ref "R7") (pin "2") (pinfunction "2_2") (pintype "passive"))
    )
    (net (code "70") (name "Net-(PWR_ISOB-A)") (class "Default")
      (node (ref "PWR_ISO") (pin "A2") (pinfunction "A_A2") (pintype "passive"))
      (node (ref "R4") (pin "2") (pinfunction "2_2") (pintype "passive"))
    )
    (net (code "71") (name "Net-(Q1-PadD)") (class "Default")
      (node (ref "Q1") (pin "D") (pinfunction "D_D") (pintype "bidirectional"))
      (node (ref "VDD_AUX") (pin "1") (pinfunction "1_1") (pintype "passive"))
    )
    (net (code "72") (name "Net-(U1-FB)") (class "Default")
      (node (ref "C2") (pin "2") (pinfunction "2_2") (pintype "passive"))
      (node (ref "R5") (pin "2") (pinfunction "2_2") (pintype "passive"))
      (node (ref "R6") (pin "1") (pinfunction "1_1") (pintype "passive"))
      (node (ref "U1") (pin "2") (pinfunction "FB_2") (pintype "input"))
    )
    (net (code "73") (name "Net-(U1-NR{slash}SS)") (class "Default")
      (node (ref "C7") (pin "1") (pinfunction "1_1") (pintype "passive"))
      (node (ref "U1") (pin "6") (pinfunction "NR/SS_6") (pintype "input"))
    )
    (net (code "74") (name "Net-(U2-NR)") (class "Default")
      (node (ref "C6") (pin "1") (pinfunction "1_1") (pintype "passive"))
      (node (ref "U2") (pin "4") (pinfunction "NR_4") (pintype "passive"))
    )
    (net (code "75") (name "Net-(U4-DIN2)") (class "Default")
      (node (ref "R10") (pin "2") (pinfunction "2_2") (pintype "passive"))
      (node (ref "U4") (pin "3") (pinfunction "DIN2_3") (pintype "bidirectional"))
    )
    (net (code "76") (name "Net-(U6-+VO)") (class "Default")
      (node (ref "C14") (pin "1") (pinfunction "1_1") (pintype "passive"))
      (node (ref "L1") (pin "1") (pinfunction "1_1") (pintype "passive"))
      (node (ref "U6") (pin "P4") (pinfunction "+VO_P4") (pintype "bidirectional"))
    )
    (net (code "77") (name "Net-(U7-FB)") (class "Default")
      (node (ref "C23") (pin "2") (pinfunction "2_2") (pintype "passive"))
      (node (ref "R12") (pin "2") (pinfunction "2_2") (pintype "passive"))
      (node (ref "R13") (pin "1") (pinfunction "1_1") (pintype "passive"))
      (node (ref "U7") (pin "2") (pinfunction "FB_2") (pintype "input"))
    )
    (net (code "78") (name "Net-(U7-NR{slash}SS)") (class "Default")
      (node (ref "C22") (pin "1") (pinfunction "1_1") (pintype "passive"))
      (node (ref "U7") (pin "6") (pinfunction "NR/SS_6") (pintype "input"))
    )
    (net (code "79") (name "unconnected-(FMC-PadP$1)") (class "Default")
      (node (ref "FMC") (pin "P$1") (pinfunction "P$1_P$1") (pintype "bidirectional"))
    )
    (net (code "80") (name "unconnected-(FMC-PadP$2)") (class "Default")
      (node (ref "FMC") (pin "P$2") (pinfunction "P$2_P$2") (pintype "bidirectional"))
    )
    (net (code "81") (name "unconnected-(FMC-PadP$4)") (class "Default")
      (node (ref "FMC") (pin "P$4") (pinfunction "P$4_P$4") (pintype "bidirectional"))
    )
    (net (code "82") (name "unconnected-(FMC-PadP$5)") (class "Default")
      (node (ref "FMC") (pin "P$5") (pinfunction "P$5_P$5") (pintype "bidirectional"))
    )
    (net (code "83") (name "unconnected-(FMC-PadP$7)") (class "Default")
      (node (ref "FMC") (pin "P$7") (pinfunction "P$7_P$7") (pintype "bidirectional"))
    )
    (net (code "84") (name "unconnected-(FMC-PadP$8)") (class "Default")
      (node (ref "FMC") (pin "P$8") (pinfunction "P$8_P$8") (pintype "bidirectional"))
    )
    (net (code "85") (name "unconnected-(FMC-PadP$10)") (class "Default")
      (node (ref "FMC") (pin "P$10") (pinfunction "P$10_P$10") (pintype "bidirectional"))
    )
    (net (code "86") (name "unconnected-(FMC-PadP$11)") (class "Default")
      (node (ref "FMC") (pin "P$11") (pinfunction "P$11_P$11") (pintype "bidirectional"))
    )
    (net (code "87") (name "unconnected-(FMC-PadP$40)") (class "Default")
      (node (ref "FMC") (pin "P$40") (pinfunction "P$40_P$40") (pintype "bidirectional"))
    )
    (net (code "88") (name "unconnected-(FMC-PadP$42)") (class "Default")
      (node (ref "FMC") (pin "P$42") (pinfunction "P$42_P$42") (pintype "bidirectional"))
    )
    (net (code "89") (name "unconnected-(FMC-PadP$43)") (class "Default")
      (node (ref "FMC") (pin "P$43") (pinfunction "P$43_P$43") (pintype "bidirectional"))
    )
    (net (code "90") (name "unconnected-(FMC-PadP$46)") (class "Default")
      (node (ref "FMC") (pin "P$46") (pinfunction "P$46_P$46") (pintype "bidirectional"))
    )
    (net (code "91") (name "unconnected-(FMC-PadP$47)") (class "Default")
      (node (ref "FMC") (pin "P$47") (pinfunction "P$47_P$47") (pintype "bidirectional"))
    )
    (net (code "92") (name "unconnected-(FMC-PadP$68)") (class "Default")
      (node (ref "FMC") (pin "P$68") (pinfunction "P$68_P$68") (pintype "bidirectional"))
    )
    (net (code "93") (name "unconnected-(FMC-PadP$70)") (class "Default")
      (node (ref "FMC") (pin "P$70") (pinfunction "P$70_P$70") (pintype "bidirectional"))
    )
    (net (code "94") (name "unconnected-(FMC-PadP$71)") (class "Default")
      (node (ref "FMC") (pin "P$71") (pinfunction "P$71_P$71") (pintype "bidirectional"))
    )
    (net (code "95") (name "unconnected-(FMC-PadP$73)") (class "Default")
      (node (ref "FMC") (pin "P$73") (pinfunction "P$73_P$73") (pintype "bidirectional"))
    )
    (net (code "96") (name "unconnected-(FMC-PadP$74)") (class "Default")
      (node (ref "FMC") (pin "P$74") (pinfunction "P$74_P$74") (pintype "bidirectional"))
    )
    (net (code "97") (name "unconnected-(FMC-PadP$76)") (class "Default")
      (node (ref "FMC") (pin "P$76") (pinfunction "P$76_P$76") (pintype "bidirectional"))
    )
    (net (code "98") (name "unconnected-(FMC-PadP$77)") (class "Default")
      (node (ref "FMC") (pin "P$77") (pinfunction "P$77_P$77") (pintype "bidirectional"))
    )
    (net (code "99") (name "unconnected-(FMC-PadP$79)") (class "Default")
      (node (ref "FMC") (pin "P$79") (pinfunction "P$79_P$79") (pintype "bidirectional"))
    )
    (net (code "100") (name "unconnected-(FMC-PadP$81)") (class "Default")
      (node (ref "FMC") (pin "P$81") (pinfunction "P$81_P$81") (pintype "bidirectional"))
    )
    (net (code "101") (name "unconnected-(FMC-PadP$84)") (class "Default")
      (node (ref "FMC") (pin "P$84") (pinfunction "P$84_P$84") (pintype "bidirectional"))
    )
    (net (code "102") (name "unconnected-(FMC-PadP$85)") (class "Default")
      (node (ref "FMC") (pin "P$85") (pinfunction "P$85_P$85") (pintype "bidirectional"))
    )
    (net (code "103") (name "unconnected-(FMC-PadP$88)") (class "Default")
      (node (ref "FMC") (pin "P$88") (pinfunction "P$88_P$88") (pintype "bidirectional"))
    )
    (net (code "104") (name "unconnected-(FMC-PadP$89)") (class "Default")
      (node (ref "FMC") (pin "P$89") (pinfunction "P$89_P$89") (pintype "bidirectional"))
    )
    (net (code "105") (name "unconnected-(FMC-PadP$91)") (class "Default")
      (node (ref "FMC") (pin "P$91") (pinfunction "P$91_P$91") (pintype "bidirectional"))
    )
    (net (code "106") (name "unconnected-(FMC-PadP$92)") (class "Default")
      (node (ref "FMC") (pin "P$92") (pinfunction "P$92_P$92") (pintype "bidirectional"))
    )
    (net (code "107") (name "unconnected-(FMC-PadP$94)") (class "Default")
      (node (ref "FMC") (pin "P$94") (pinfunction "P$94_P$94") (pintype "bidirectional"))
    )
    (net (code "108") (name "unconnected-(FMC-PadP$95)") (class "Default")
      (node (ref "FMC") (pin "P$95") (pinfunction "P$95_P$95") (pintype "bidirectional"))
    )
    (net (code "109") (name "unconnected-(FMC-PadP$97)") (class "Default")
      (node (ref "FMC") (pin "P$97") (pinfunction "P$97_P$97") (pintype "bidirectional"))
    )
    (net (code "110") (name "unconnected-(FMC-PadP$98)") (class "Default")
      (node (ref "FMC") (pin "P$98") (pinfunction "P$98_P$98") (pintype "bidirectional"))
    )
    (net (code "111") (name "unconnected-(FMC-PadP$100)") (class "Default")
      (node (ref "FMC") (pin "P$100") (pinfunction "P$100_P$100") (pintype "bidirectional"))
    )
    (net (code "112") (name "unconnected-(FMC-PadP$101)") (class "Default")
      (node (ref "FMC") (pin "P$101") (pinfunction "P$101_P$101") (pintype "bidirectional"))
    )
    (net (code "113") (name "unconnected-(FMC-PadP$103)") (class "Default")
      (node (ref "FMC") (pin "P$103") (pinfunction "P$103_P$103") (pintype "bidirectional"))
    )
    (net (code "114") (name "unconnected-(FMC-PadP$104)") (class "Default")
      (node (ref "FMC") (pin "P$104") (pinfunction "P$104_P$104") (pintype "bidirectional"))
    )
    (net (code "115") (name "unconnected-(FMC-PadP$106)") (class "Default")
      (node (ref "FMC") (pin "P$106") (pinfunction "P$106_P$106") (pintype "bidirectional"))
    )
    (net (code "116") (name "unconnected-(FMC-PadP$107)") (class "Default")
      (node (ref "FMC") (pin "P$107") (pinfunction "P$107_P$107") (pintype "bidirectional"))
    )
    (net (code "117") (name "unconnected-(FMC-PadP$109)") (class "Default")
      (node (ref "FMC") (pin "P$109") (pinfunction "P$109_P$109") (pintype "bidirectional"))
    )
    (net (code "118") (name "unconnected-(FMC-PadP$112)") (class "Default")
      (node (ref "FMC") (pin "P$112") (pinfunction "P$112_P$112") (pintype "bidirectional"))
    )
    (net (code "119") (name "unconnected-(FMC-PadP$113)") (class "Default")
      (node (ref "FMC") (pin "P$113") (pinfunction "P$113_P$113") (pintype "bidirectional"))
    )
    (net (code "120") (name "unconnected-(FMC-PadP$114)") (class "Default")
      (node (ref "FMC") (pin "P$114") (pinfunction "P$114_P$114") (pintype "bidirectional"))
    )
    (net (code "121") (name "unconnected-(FMC-PadP$115)") (class "Default")
      (node (ref "FMC") (pin "P$115") (pinfunction "P$115_P$115") (pintype "bidirectional"))
    )
    (net (code "122") (name "unconnected-(FMC-PadP$122)") (class "Default")
      (node (ref "FMC") (pin "P$122") (pinfunction "P$122_P$122") (pintype "bidirectional"))
    )
    (net (code "123") (name "unconnected-(FMC-PadP$123)") (class "Default")
      (node (ref "FMC") (pin "P$123") (pinfunction "P$123_P$123") (pintype "bidirectional"))
    )
    (net (code "124") (name "unconnected-(FMC-PadP$126)") (class "Default")
      (node (ref "FMC") (pin "P$126") (pinfunction "P$126_P$126") (pintype "bidirectional"))
    )
    (net (code "125") (name "unconnected-(FMC-PadP$127)") (class "Default")
      (node (ref "FMC") (pin "P$127") (pinfunction "P$127_P$127") (pintype "bidirectional"))
    )
    (net (code "126") (name "unconnected-(FMC-PadP$130)") (class "Default")
      (node (ref "FMC") (pin "P$130") (pinfunction "P$130_P$130") (pintype "bidirectional"))
    )
    (net (code "127") (name "unconnected-(FMC-PadP$131)") (class "Default")
      (node (ref "FMC") (pin "P$131") (pinfunction "P$131_P$131") (pintype "bidirectional"))
    )
    (net (code "128") (name "unconnected-(FMC-PadP$134)") (class "Default")
      (node (ref "FMC") (pin "P$134") (pinfunction "P$134_P$134") (pintype "bidirectional"))
    )
    (net (code "129") (name "unconnected-(FMC-PadP$135)") (class "Default")
      (node (ref "FMC") (pin "P$135") (pinfunction "P$135_P$135") (pintype "bidirectional"))
    )
    (net (code "130") (name "unconnected-(FMC-PadP$138)") (class "Default")
      (node (ref "FMC") (pin "P$138") (pinfunction "P$138_P$138") (pintype "bidirectional"))
    )
    (net (code "131") (name "unconnected-(FMC-PadP$139)") (class "Default")
      (node (ref "FMC") (pin "P$139") (pinfunction "P$139_P$139") (pintype "bidirectional"))
    )
    (net (code "132") (name "unconnected-(FMC-PadP$142)") (class "Default")
      (node (ref "FMC") (pin "P$142") (pinfunction "P$142_P$142") (pintype "bidirectional"))
    )
    (net (code "133") (name "unconnected-(FMC-PadP$143)") (class "Default")
      (node (ref "FMC") (pin "P$143") (pinfunction "P$143_P$143") (pintype "bidirectional"))
    )
    (net (code "134") (name "unconnected-(FMC-PadP$146)") (class "Default")
      (node (ref "FMC") (pin "P$146") (pinfunction "P$146_P$146") (pintype "bidirectional"))
    )
    (net (code "135") (name "unconnected-(FMC-PadP$147)") (class "Default")
      (node (ref "FMC") (pin "P$147") (pinfunction "P$147_P$147") (pintype "bidirectional"))
    )
    (net (code "136") (name "unconnected-(FMC-PadP$150)") (class "Default")
      (node (ref "FMC") (pin "P$150") (pinfunction "P$150_P$150") (pintype "bidirectional"))
    )
    (net (code "137") (name "unconnected-(FMC-PadP$151)") (class "Default")
      (node (ref "FMC") (pin "P$151") (pinfunction "P$151_P$151") (pintype "bidirectional"))
    )
    (net (code "138") (name "unconnected-(FMC-PadP$154)") (class "Default")
      (node (ref "FMC") (pin "P$154") (pinfunction "P$154_P$154") (pintype "bidirectional"))
    )
    (net (code "139") (name "unconnected-(U1-DNC-Pad7)") (class "Default")
      (node (ref "U1") (pin "7") (pinfunction "DNC_7") (pintype "no_connect"))
    )
    (net (code "140") (name "unconnected-(U1-NC-Pad3)") (class "Default")
      (node (ref "U1") (pin "3") (pinfunction "NC_3") (pintype "no_connect"))
    )
    (net (code "141") (name "unconnected-(U4-DOUT2+-Pad6)") (class "Default")
      (node (ref "U4") (pin "6") (pinfunction "DOUT2+_6") (pintype "bidirectional"))
    )
    (net (code "142") (name "unconnected-(U4-DOUT2--Pad5)") (class "Default")
      (node (ref "U4") (pin "5") (pinfunction "DOUT2-_5") (pintype "bidirectional"))
    )
    (net (code "143") (name "unconnected-(U7-DNC-Pad7)") (class "Default")
      (node (ref "U7") (pin "7") (pinfunction "DNC_7") (pintype "no_connect"))
    )
    (net (code "144") (name "unconnected-(U7-NC-Pad3)") (class "Default")
      (node (ref "U7") (pin "3") (pinfunction "NC_3") (pintype "no_connect"))
    )
    (net (code "145") (name "unconnected-(U8-PadBEZ1)") (class "Default")
      (node (ref "U8") (pin "BEZ1") (pinfunction "BEZ1_BEZ1") (pintype "bidirectional"))
    )
    (net (code "146") (name "unconnected-(U8-PadBEZ2)") (class "Default")
      (node (ref "U8") (pin "BEZ2") (pinfunction "BEZ2_BEZ2") (pintype "bidirectional"))
    )
  )
)
